# 1_flatsat_interfaces.net
KiCad netlist of a schematic drawn in Altium Designer
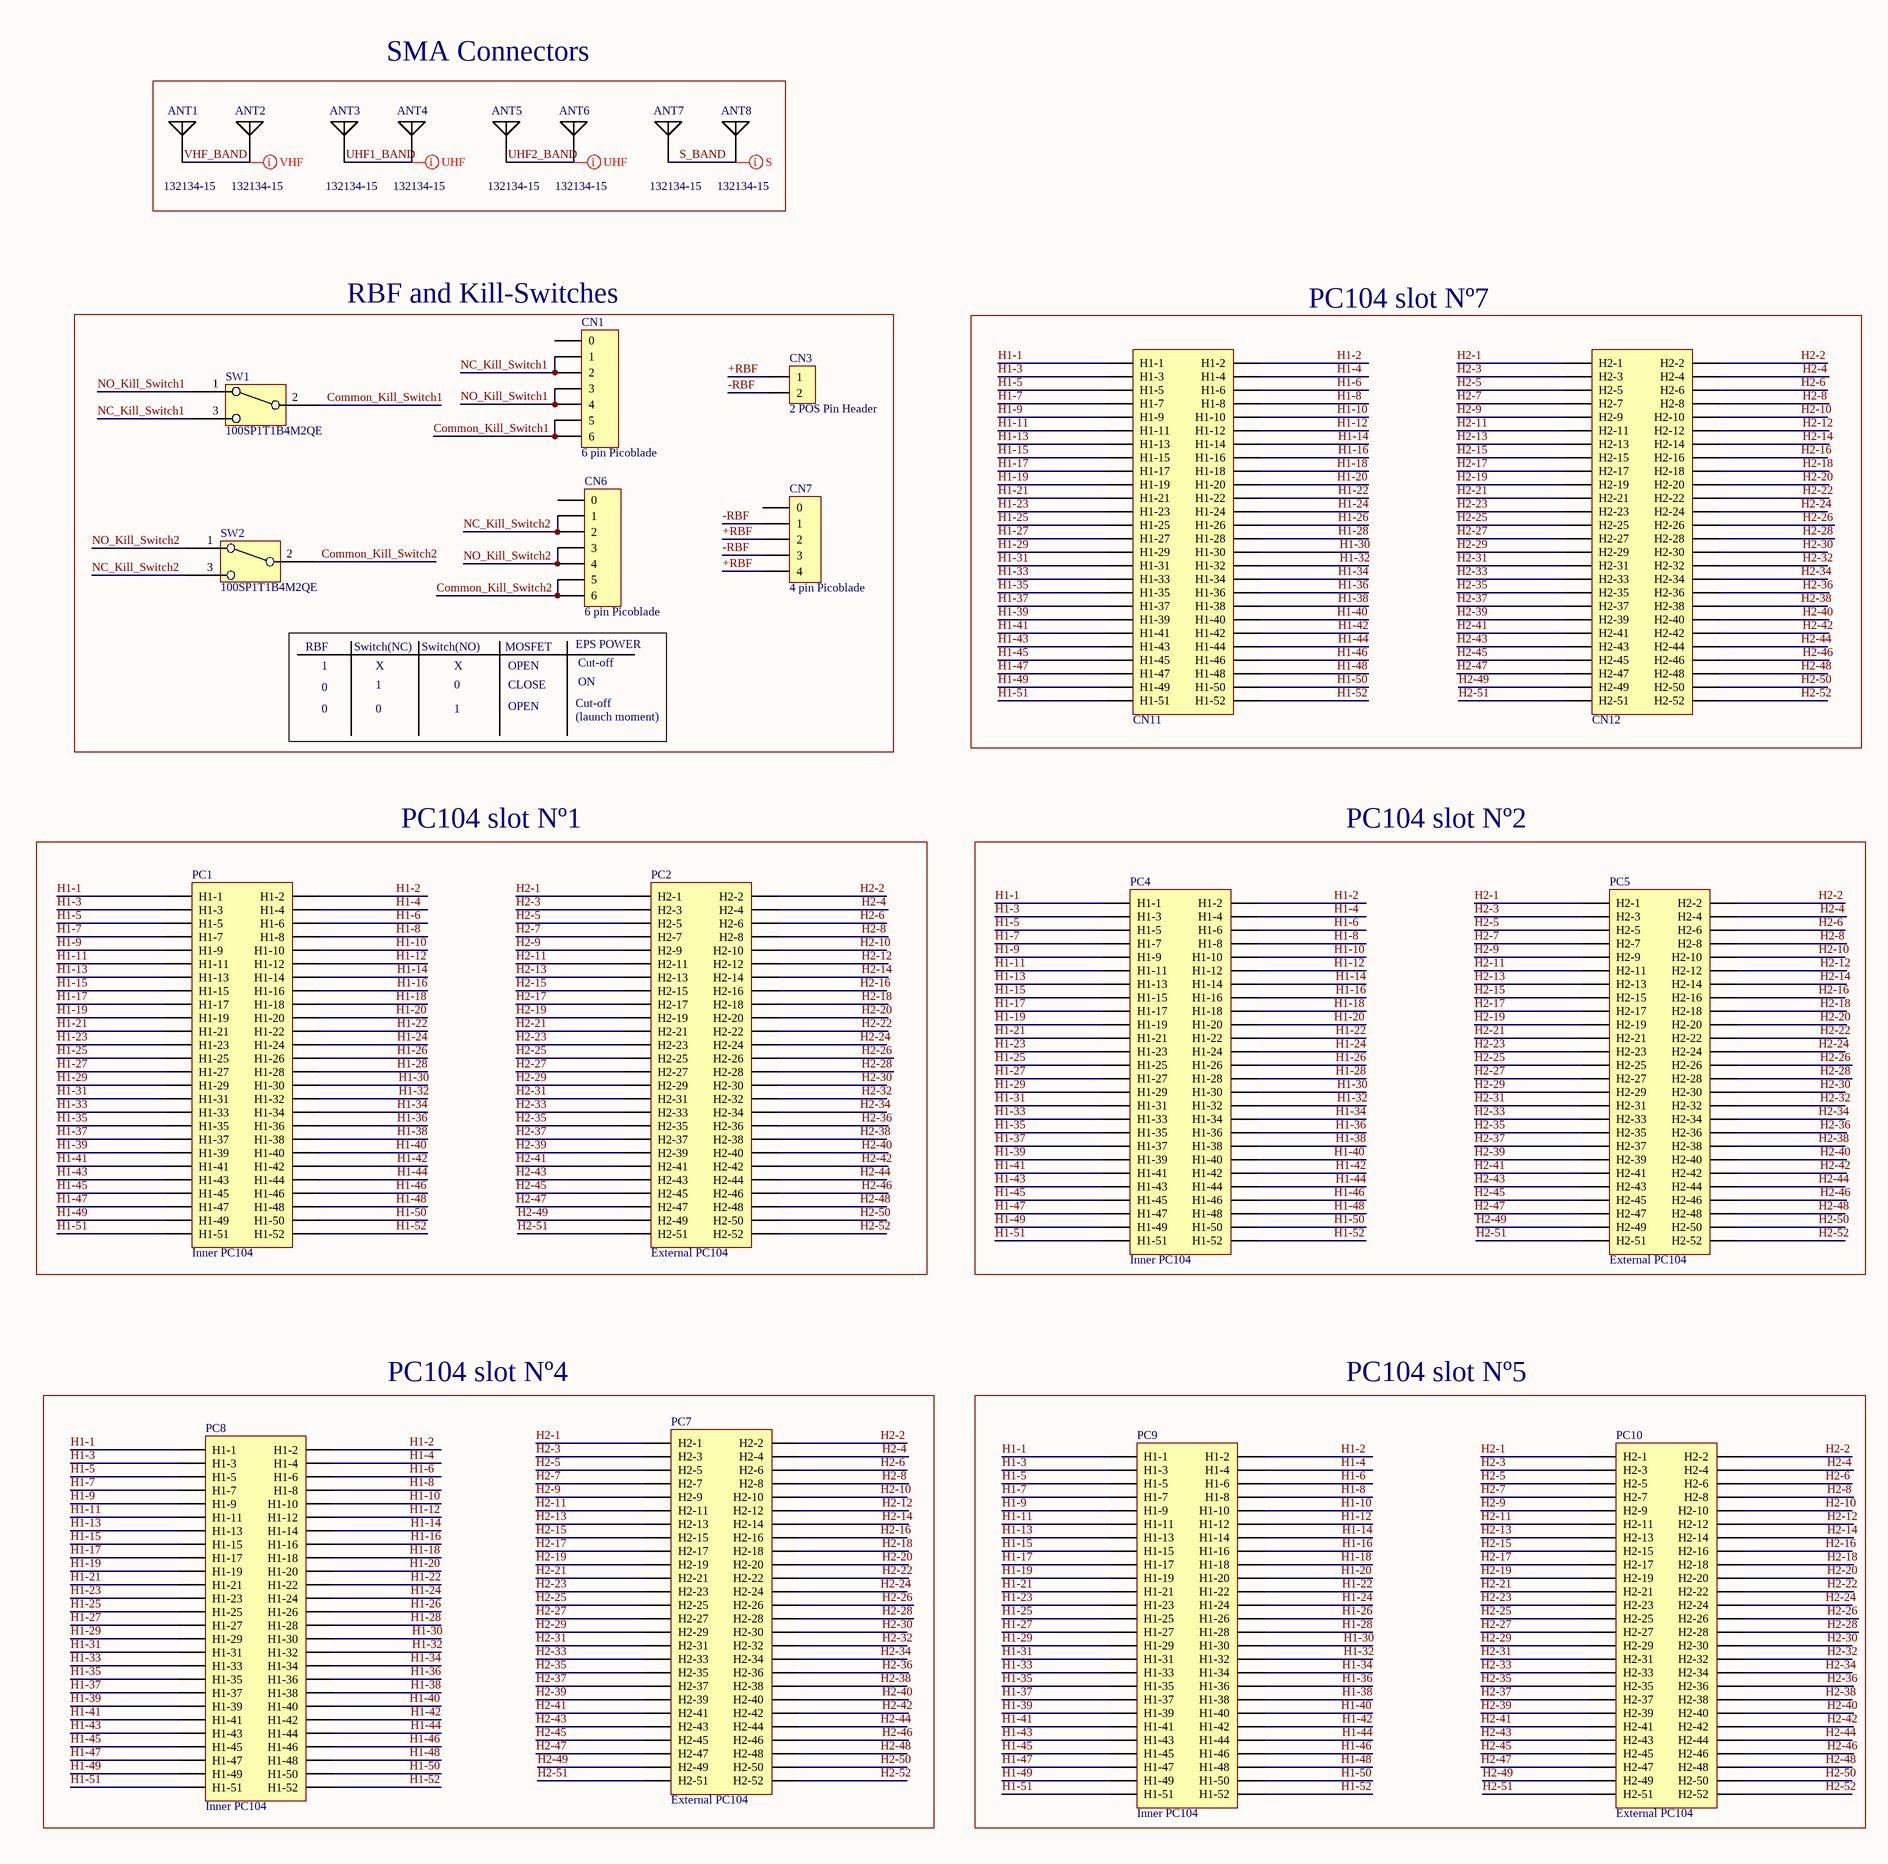
[diagram p0: 1_flatsat_interfaces.SchDoc, left]
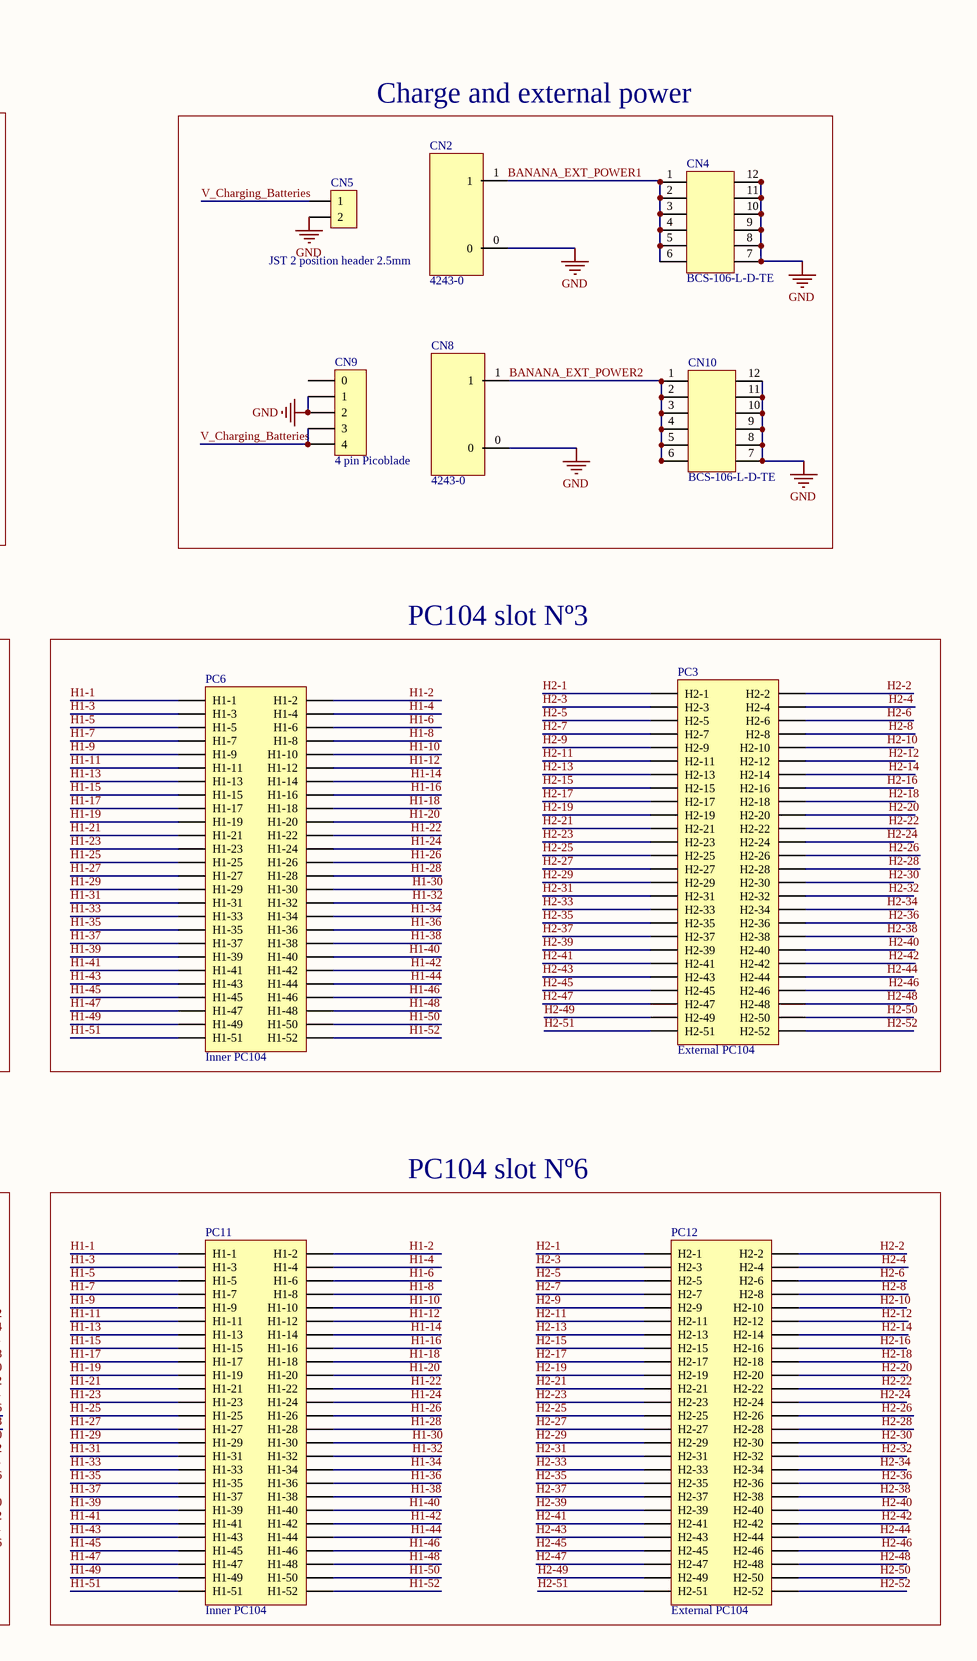
[diagram p1: 1_flatsat_interfaces.SchDoc, right]

(export (version "E")
  (design (tool "Eeschema 10.0.6"))
  (components
    (comp (ref "ANT1")
      (value "132134-15")
      (footprint "132134-15")
      (libsource (lib "flatsat_platform") (part "132134-15"))
    )
    (comp (ref "ANT2")
      (value "132134-15")
      (footprint "132134-15")
      (libsource (lib "flatsat_platform") (part "132134-15"))
    )
    (comp (ref "ANT3")
      (value "132134-15")
      (footprint "132134-15")
      (libsource (lib "flatsat_platform") (part "132134-15"))
    )
    (comp (ref "ANT4")
      (value "132134-15")
      (footprint "132134-15")
      (libsource (lib "flatsat_platform") (part "132134-15"))
    )
    (comp (ref "ANT5")
      (value "132134-15")
      (footprint "132134-15")
      (libsource (lib "flatsat_platform") (part "132134-15"))
    )
    (comp (ref "ANT6")
      (value "132134-15")
      (footprint "132134-15")
      (libsource (lib "flatsat_platform") (part "132134-15"))
    )
    (comp (ref "ANT7")
      (value "132134-15")
      (footprint "132134-15")
      (libsource (lib "flatsat_platform") (part "132134-15"))
    )
    (comp (ref "ANT8")
      (value "132134-15")
      (footprint "132134-15")
      (libsource (lib "flatsat_platform") (part "132134-15"))
    )
    (comp (ref "CN1")
      (value "6 pin Picoblade")
      (footprint "PICO BLADE 0533980671")
      (description "1.25mm Pitch PicoBlade™ Header, Surface Mount, Vertical, 6 Circuits")
      (fields (field (name "MANUFACTURER") "Molex") (field (name "MANUFACTURER PART NUMBER") "53398-0671"))
      (libsource (lib "flatsat_platform") (part "53398-0671"))
    )
    (comp (ref "CN2")
      (value "4243-0")
      (footprint "4243-0")
      (description "POMONA, 4243-0, Binding Post, 4243 Series, 15 A, 60 VDC, Tin Plated Contacts, Brass, Black")
      (fields (field (name "MANUFACTURER") "Pomona Electronics"))
      (libsource (lib "flatsat_platform") (part "4243-0"))
    )
    (comp (ref "CN3")
      (value "2 POS Pin Header")
      (footprint "CONN HEADER VERT 2POS 2.54mm")
      (description "M20 HDR, PIN, SIL, VERT, 2W")
      (fields (field (name "MANUFACTURER") "Harwin") (field (name "VOLTAGE") "50V"))
      (libsource (lib "flatsat_platform") (part "M20-9990245"))
    )
    (comp (ref "CN4")
      (value "BCS-106-L-D-TE")
      (footprint "BCS-106-L-D-TE")
      (description "CONN RCPT 12POS 0.1 GOLD PCB")
      (fields (field (name "MANUFACTURER") "Samtec"))
      (libsource (lib "flatsat_platform") (part "BCS-106-L-D-TE"))
    )
    (comp (ref "CN5")
      (value "JST 2 position header 2.5mm")
      (footprint "B2B-XH-A-M(LF)(SN)")
      (description "CONN HEADER TOP 2POS 2.5MM GRN")
      (fields
        (field (name "MANUFACTURER") "JST")
        (field (name "MANUFACTURER PART NUMBER") "B2B-XH-A-M(LF)(SN)")
      )
      (libsource (lib "flatsat_platform") (part "B2B-XH-A-M(LF)(SN)"))
    )
    (comp (ref "CN6")
      (value "6 pin Picoblade")
      (footprint "PICO BLADE 0533980671")
      (description "1.25mm Pitch PicoBlade™ Header, Surface Mount, Vertical, 6 Circuits")
      (fields (field (name "MANUFACTURER") "Molex") (field (name "MANUFACTURER PART NUMBER") "53398-0671"))
      (libsource (lib "flatsat_platform") (part "53398-0671"))
    )
    (comp (ref "CN7")
      (value "4 pin Picoblade")
      (footprint "PICO BLADE 0533980471")
      (description "Connector Header Surface Mount 4 position 0.049\" (1.25mm)")
      (fields (field (name "MANUFACTURER") "Molex") (field (name "MANUFACTURER PART NUMBER") "53398-0471"))
      (libsource (lib "flatsat_platform") (part "0533980471"))
    )
    (comp (ref "CN8")
      (value "4243-0")
      (footprint "4243-0")
      (description "POMONA, 4243-0, Binding Post, 4243 Series, 15 A, 60 VDC, Tin Plated Contacts, Brass, Black")
      (fields (field (name "MANUFACTURER") "Pomona Electronics"))
      (libsource (lib "flatsat_platform") (part "4243-0"))
    )
    (comp (ref "CN9")
      (value "4 pin Picoblade")
      (footprint "PICO BLADE 0533980471")
      (description "Connector Header Surface Mount 4 position 0.049\" (1.25mm)")
      (fields (field (name "MANUFACTURER") "Molex") (field (name "MANUFACTURER PART NUMBER") "53398-0471"))
      (libsource (lib "flatsat_platform") (part "0533980471"))
    )
    (comp (ref "CN10")
      (value "BCS-106-L-D-TE")
      (footprint "BCS-106-L-D-TE")
      (description "CONN RCPT 12POS 0.1 GOLD PCB")
      (fields (field (name "MANUFACTURER") "Samtec"))
      (libsource (lib "flatsat_platform") (part "BCS-106-L-D-TE"))
    )
    (comp (ref "CN11")
      (value "CONN RCPT 52POS 0.1 GOLD PCB")
      (footprint "Inner_SSW-126-01-G-D_testboard")
      (description "Conn Socket Strip SKT 52 POS 2.54mm Solder ST Thru-Hole")
      (fields
        (field (name "MANUFACTURER") "Samtec")
        (field (name "MANUFACTURER PART NUMBER") "SSW-126-01-G-D")
      )
      (libsource (lib "flatsat_platform") (part "Inner_Expansion_TestBoard_PC104"))
    )
    (comp (ref "CN12")
      (value "CONN RCPT 52POS 0.1 GOLD PCB")
      (footprint "external_SSW-126-01-G-D _testboard")
      (description "Conn Socket Strip SKT 52 POS 2.54mm Solder ST Thru-Hole")
      (fields
        (field (name "MANUFACTURER") "Samtec")
        (field (name "MANUFACTURER PART NUMBER") "SSW-126-01-G-D")
      )
      (libsource (lib "flatsat_platform") (part "External_Expansion_TestBoard_PC104"))
    )
    (comp (ref "PC1")
      (value "Inner PC104")
      (footprint "Inner_SSW-126-01-G-D")
      (description "52 Position Receptacle Connector  Through Hole")
      (fields (field (name "PARTNUMBER") "SSW-126-01-G-D") (field (name "MANUFACTURER") "Samtec"))
      (libsource (lib "flatsat_platform") (part "Inner_SSW-126-01-G-D"))
    )
    (comp (ref "PC2")
      (value "External PC104")
      (footprint "external_SSW-126-01-G-D")
      (description "52 Position Receptacle Connector  Through Hole")
      (fields (field (name "PARTNUMBER") "SSW-126-01-G-D") (field (name "MANUFACTURER") "Samtec"))
      (libsource (lib "flatsat_platform") (part "External_SSW-126-01-G-D_1"))
    )
    (comp (ref "PC3")
      (value "External PC104")
      (footprint "external_SSW-126-01-G-D")
      (description "52 Position Receptacle Connector  Through Hole")
      (fields (field (name "PARTNUMBER") "SSW-126-01-G-D") (field (name "MANUFACTURER") "Samtec"))
      (libsource (lib "flatsat_platform") (part "External_SSW-126-01-G-D_1"))
    )
    (comp (ref "PC4")
      (value "Inner PC104")
      (footprint "Inner_SSW-126-01-G-D")
      (description "52 Position Receptacle Connector  Through Hole")
      (fields (field (name "PARTNUMBER") "SSW-126-01-G-D") (field (name "MANUFACTURER") "Samtec"))
      (libsource (lib "flatsat_platform") (part "Inner_SSW-126-01-G-D"))
    )
    (comp (ref "PC5")
      (value "External PC104")
      (footprint "external_SSW-126-01-G-D")
      (description "52 Position Receptacle Connector  Through Hole")
      (fields (field (name "PARTNUMBER") "SSW-126-01-G-D") (field (name "MANUFACTURER") "Samtec"))
      (libsource (lib "flatsat_platform") (part "External_SSW-126-01-G-D_1"))
    )
    (comp (ref "PC6")
      (value "Inner PC104")
      (footprint "Inner_SSW-126-01-G-D")
      (description "52 Position Receptacle Connector  Through Hole")
      (fields (field (name "PARTNUMBER") "SSW-126-01-G-D") (field (name "MANUFACTURER") "Samtec"))
      (libsource (lib "flatsat_platform") (part "Inner_SSW-126-01-G-D"))
    )
    (comp (ref "PC7")
      (value "External PC104")
      (footprint "external_SSW-126-01-G-D")
      (description "52 Position Receptacle Connector  Through Hole")
      (fields (field (name "PARTNUMBER") "SSW-126-01-G-D") (field (name "MANUFACTURER") "Samtec"))
      (libsource (lib "flatsat_platform") (part "External_SSW-126-01-G-D_1"))
    )
    (comp (ref "PC8")
      (value "Inner PC104")
      (footprint "Inner_SSW-126-01-G-D")
      (description "52 Position Receptacle Connector  Through Hole")
      (fields (field (name "PARTNUMBER") "SSW-126-01-G-D") (field (name "MANUFACTURER") "Samtec"))
      (libsource (lib "flatsat_platform") (part "Inner_SSW-126-01-G-D"))
    )
    (comp (ref "PC9")
      (value "Inner PC104")
      (footprint "Inner_SSW-126-01-G-D")
      (description "52 Position Receptacle Connector  Through Hole")
      (fields (field (name "PARTNUMBER") "SSW-126-01-G-D") (field (name "MANUFACTURER") "Samtec"))
      (libsource (lib "flatsat_platform") (part "Inner_SSW-126-01-G-D"))
    )
    (comp (ref "PC10")
      (value "External PC104")
      (footprint "external_SSW-126-01-G-D")
      (description "52 Position Receptacle Connector  Through Hole")
      (fields (field (name "PARTNUMBER") "SSW-126-01-G-D") (field (name "MANUFACTURER") "Samtec"))
      (libsource (lib "flatsat_platform") (part "External_SSW-126-01-G-D_1"))
    )
    (comp (ref "PC11")
      (value "Inner PC104")
      (footprint "Inner_SSW-126-01-G-D")
      (description "52 Position Receptacle Connector  Through Hole")
      (fields (field (name "PARTNUMBER") "SSW-126-01-G-D") (field (name "MANUFACTURER") "Samtec"))
      (libsource (lib "flatsat_platform") (part "Inner_SSW-126-01-G-D"))
    )
    (comp (ref "PC12")
      (value "External PC104")
      (footprint "external_SSW-126-01-G-D")
      (description "52 Position Receptacle Connector  Through Hole")
      (fields (field (name "PARTNUMBER") "SSW-126-01-G-D") (field (name "MANUFACTURER") "Samtec"))
      (libsource (lib "flatsat_platform") (part "External_SSW-126-01-G-D_1"))
    )
    (comp (ref "SW1")
      (value "100SP1T1B4M2QE")
      (footprint "Toggle Switch SPDT Through Hole")
      (description "E-SWITCH - 100SP1T1B4M2QE - SWITCH, TOGGLE, SPDT, 5A, 120VAC, 28VDC")
      (libsource (lib "flatsat_platform") (part "100SP1T1B4M2QE"))
    )
    (comp (ref "SW2")
      (value "100SP1T1B4M2QE")
      (footprint "Toggle Switch SPDT Through Hole")
      (description "E-SWITCH - 100SP1T1B4M2QE - SWITCH, TOGGLE, SPDT, 5A, 120VAC, 28VDC")
      (libsource (lib "flatsat_platform") (part "100SP1T1B4M2QE"))
    )
  )
  (nets
    (net (code "1") (name "/+RBF") (class "Default")
      (node (ref "CN3") (pin "1") (pinfunction "1_1") (pintype "passive"))
      (node (ref "CN7") (pin "2") (pinfunction "2_2") (pintype "passive"))
      (node (ref "CN7") (pin "4") (pinfunction "4_4") (pintype "passive"))
    )
    (net (code "2") (name "/-RBF") (class "Default")
      (node (ref "CN3") (pin "2") (pinfunction "2_2") (pintype "passive"))
      (node (ref "CN7") (pin "1") (pinfunction "1_1") (pintype "passive"))
      (node (ref "CN7") (pin "3") (pinfunction "3_3") (pintype "passive"))
    )
    (net (code "3") (name "/BANANA_EXT_POWER1") (class "Default")
      (node (ref "CN2") (pin "1") (pinfunction "1_1") (pintype "passive"))
      (node (ref "CN4") (pin "1") (pintype "passive"))
      (node (ref "CN4") (pin "2") (pintype "passive"))
      (node (ref "CN4") (pin "3") (pintype "passive"))
      (node (ref "CN4") (pin "4") (pintype "passive"))
      (node (ref "CN4") (pin "5") (pintype "passive"))
      (node (ref "CN4") (pin "6") (pintype "passive"))
    )
    (net (code "4") (name "/BANANA_EXT_POWER2") (class "Default")
      (node (ref "CN10") (pin "1") (pintype "passive"))
      (node (ref "CN10") (pin "2") (pintype "passive"))
      (node (ref "CN10") (pin "3") (pintype "passive"))
      (node (ref "CN10") (pin "4") (pintype "passive"))
      (node (ref "CN10") (pin "5") (pintype "passive"))
      (node (ref "CN10") (pin "6") (pintype "passive"))
      (node (ref "CN8") (pin "1") (pinfunction "1_1") (pintype "passive"))
    )
    (net (code "5") (name "/Common_Kill_Switch1") (class "Default")
      (node (ref "CN1") (pin "5") (pinfunction "5_5") (pintype "passive"))
      (node (ref "CN1") (pin "6") (pinfunction "6_6") (pintype "passive"))
      (node (ref "SW1") (pin "2") (pinfunction "C_2") (pintype "passive"))
    )
    (net (code "6") (name "/Common_Kill_Switch2") (class "Default")
      (node (ref "CN6") (pin "5") (pinfunction "5_5") (pintype "passive"))
      (node (ref "CN6") (pin "6") (pinfunction "6_6") (pintype "passive"))
      (node (ref "SW2") (pin "2") (pinfunction "C_2") (pintype "passive"))
    )
    (net (code "7") (name "/H1-1") (class "Default")
      (node (ref "CN11") (pin "H1-1") (pinfunction "H1-1_H1-1") (pintype "passive"))
      (node (ref "PC1") (pin "H1-1") (pinfunction "H1-1_H1-1") (pintype "passive"))
      (node (ref "PC11") (pin "H1-1") (pinfunction "H1-1_H1-1") (pintype "passive"))
      (node (ref "PC4") (pin "H1-1") (pinfunction "H1-1_H1-1") (pintype "passive"))
      (node (ref "PC6") (pin "H1-1") (pinfunction "H1-1_H1-1") (pintype "passive"))
      (node (ref "PC8") (pin "H1-1") (pinfunction "H1-1_H1-1") (pintype "passive"))
      (node (ref "PC9") (pin "H1-1") (pinfunction "H1-1_H1-1") (pintype "passive"))
    )
    (net (code "8") (name "/H1-2") (class "Default")
      (node (ref "CN11") (pin "H1-2") (pinfunction "H1-2_H1-2") (pintype "passive"))
      (node (ref "PC1") (pin "H1-2") (pinfunction "H1-2_H1-2") (pintype "passive"))
      (node (ref "PC11") (pin "H1-2") (pinfunction "H1-2_H1-2") (pintype "passive"))
      (node (ref "PC4") (pin "H1-2") (pinfunction "H1-2_H1-2") (pintype "passive"))
      (node (ref "PC6") (pin "H1-2") (pinfunction "H1-2_H1-2") (pintype "passive"))
      (node (ref "PC8") (pin "H1-2") (pinfunction "H1-2_H1-2") (pintype "passive"))
      (node (ref "PC9") (pin "H1-2") (pinfunction "H1-2_H1-2") (pintype "passive"))
    )
    (net (code "9") (name "/H1-3") (class "Default")
      (node (ref "CN11") (pin "H1-3") (pinfunction "H1-3_H1-3") (pintype "passive"))
      (node (ref "PC1") (pin "H1-3") (pinfunction "H1-3_H1-3") (pintype "passive"))
      (node (ref "PC11") (pin "H1-3") (pinfunction "H1-3_H1-3") (pintype "passive"))
      (node (ref "PC4") (pin "H1-3") (pinfunction "H1-3_H1-3") (pintype "passive"))
      (node (ref "PC6") (pin "H1-3") (pinfunction "H1-3_H1-3") (pintype "passive"))
      (node (ref "PC8") (pin "H1-3") (pinfunction "H1-3_H1-3") (pintype "passive"))
      (node (ref "PC9") (pin "H1-3") (pinfunction "H1-3_H1-3") (pintype "passive"))
    )
    (net (code "10") (name "/H1-4") (class "Default")
      (node (ref "CN11") (pin "H1-4") (pinfunction "H1-4_H1-4") (pintype "passive"))
      (node (ref "PC1") (pin "H1-4") (pinfunction "H1-4_H1-4") (pintype "passive"))
      (node (ref "PC11") (pin "H1-4") (pinfunction "H1-4_H1-4") (pintype "passive"))
      (node (ref "PC4") (pin "H1-4") (pinfunction "H1-4_H1-4") (pintype "passive"))
      (node (ref "PC6") (pin "H1-4") (pinfunction "H1-4_H1-4") (pintype "passive"))
      (node (ref "PC8") (pin "H1-4") (pinfunction "H1-4_H1-4") (pintype "passive"))
      (node (ref "PC9") (pin "H1-4") (pinfunction "H1-4_H1-4") (pintype "passive"))
    )
    (net (code "11") (name "/H1-5") (class "Default")
      (node (ref "CN11") (pin "H1-5") (pinfunction "H1-5_H1-5") (pintype "passive"))
      (node (ref "PC1") (pin "H1-5") (pinfunction "H1-5_H1-5") (pintype "passive"))
      (node (ref "PC11") (pin "H1-5") (pinfunction "H1-5_H1-5") (pintype "passive"))
      (node (ref "PC4") (pin "H1-5") (pinfunction "H1-5_H1-5") (pintype "passive"))
      (node (ref "PC6") (pin "H1-5") (pinfunction "H1-5_H1-5") (pintype "passive"))
      (node (ref "PC8") (pin "H1-5") (pinfunction "H1-5_H1-5") (pintype "passive"))
      (node (ref "PC9") (pin "H1-5") (pinfunction "H1-5_H1-5") (pintype "passive"))
    )
    (net (code "12") (name "/H1-6") (class "Default")
      (node (ref "CN11") (pin "H1-6") (pinfunction "H1-6_H1-6") (pintype "passive"))
      (node (ref "PC1") (pin "H1-6") (pinfunction "H1-6_H1-6") (pintype "passive"))
      (node (ref "PC11") (pin "H1-6") (pinfunction "H1-6_H1-6") (pintype "passive"))
      (node (ref "PC4") (pin "H1-6") (pinfunction "H1-6_H1-6") (pintype "passive"))
      (node (ref "PC6") (pin "H1-6") (pinfunction "H1-6_H1-6") (pintype "passive"))
      (node (ref "PC8") (pin "H1-6") (pinfunction "H1-6_H1-6") (pintype "passive"))
      (node (ref "PC9") (pin "H1-6") (pinfunction "H1-6_H1-6") (pintype "passive"))
    )
    (net (code "13") (name "/H1-7") (class "Default")
      (node (ref "CN11") (pin "H1-7") (pinfunction "H1-7_H1-7") (pintype "passive"))
      (node (ref "PC1") (pin "H1-7") (pinfunction "H1-7_H1-7") (pintype "passive"))
      (node (ref "PC11") (pin "H1-7") (pinfunction "H1-7_H1-7") (pintype "passive"))
      (node (ref "PC4") (pin "H1-7") (pinfunction "H1-7_H1-7") (pintype "passive"))
      (node (ref "PC6") (pin "H1-7") (pinfunction "H1-7_H1-7") (pintype "passive"))
      (node (ref "PC8") (pin "H1-7") (pinfunction "H1-7_H1-7") (pintype "passive"))
      (node (ref "PC9") (pin "H1-7") (pinfunction "H1-7_H1-7") (pintype "passive"))
    )
    (net (code "14") (name "/H1-8") (class "Default")
      (node (ref "CN11") (pin "H1-8") (pinfunction "H1-8_H1-8") (pintype "passive"))
      (node (ref "PC1") (pin "H1-8") (pinfunction "H1-8_H1-8") (pintype "passive"))
      (node (ref "PC11") (pin "H1-8") (pinfunction "H1-8_H1-8") (pintype "passive"))
      (node (ref "PC4") (pin "H1-8") (pinfunction "H1-8_H1-8") (pintype "passive"))
      (node (ref "PC6") (pin "H1-8") (pinfunction "H1-8_H1-8") (pintype "passive"))
      (node (ref "PC8") (pin "H1-8") (pinfunction "H1-8_H1-8") (pintype "passive"))
      (node (ref "PC9") (pin "H1-8") (pinfunction "H1-8_H1-8") (pintype "passive"))
    )
    (net (code "15") (name "/H1-9") (class "Default")
      (node (ref "CN11") (pin "H1-9") (pinfunction "H1-9_H1-9") (pintype "passive"))
      (node (ref "PC1") (pin "H1-9") (pinfunction "H1-9_H1-9") (pintype "passive"))
      (node (ref "PC11") (pin "H1-9") (pinfunction "H1-9_H1-9") (pintype "passive"))
      (node (ref "PC4") (pin "H1-9") (pinfunction "H1-9_H1-9") (pintype "passive"))
      (node (ref "PC6") (pin "H1-9") (pinfunction "H1-9_H1-9") (pintype "passive"))
      (node (ref "PC8") (pin "H1-9") (pinfunction "H1-9_H1-9") (pintype "passive"))
      (node (ref "PC9") (pin "H1-9") (pinfunction "H1-9_H1-9") (pintype "passive"))
    )
    (net (code "16") (name "/H1-10") (class "Default")
      (node (ref "CN11") (pin "H1-10") (pinfunction "H1-10_H1-10") (pintype "passive"))
      (node (ref "PC1") (pin "H1-10") (pinfunction "H1-10_H1-10") (pintype "passive"))
      (node (ref "PC11") (pin "H1-10") (pinfunction "H1-10_H1-10") (pintype "passive"))
      (node (ref "PC4") (pin "H1-10") (pinfunction "H1-10_H1-10") (pintype "passive"))
      (node (ref "PC6") (pin "H1-10") (pinfunction "H1-10_H1-10") (pintype "passive"))
      (node (ref "PC8") (pin "H1-10") (pinfunction "H1-10_H1-10") (pintype "passive"))
      (node (ref "PC9") (pin "H1-10") (pinfunction "H1-10_H1-10") (pintype "passive"))
    )
    (net (code "17") (name "/H1-11") (class "Default")
      (node (ref "CN11") (pin "H1-11") (pinfunction "H1-11_H1-11") (pintype "passive"))
      (node (ref "PC1") (pin "H1-11") (pinfunction "H1-11_H1-11") (pintype "passive"))
      (node (ref "PC11") (pin "H1-11") (pinfunction "H1-11_H1-11") (pintype "passive"))
      (node (ref "PC4") (pin "H1-11") (pinfunction "H1-11_H1-11") (pintype "passive"))
      (node (ref "PC6") (pin "H1-11") (pinfunction "H1-11_H1-11") (pintype "passive"))
      (node (ref "PC8") (pin "H1-11") (pinfunction "H1-11_H1-11") (pintype "passive"))
      (node (ref "PC9") (pin "H1-11") (pinfunction "H1-11_H1-11") (pintype "passive"))
    )
    (net (code "18") (name "/H1-12") (class "Default")
      (node (ref "CN11") (pin "H1-12") (pinfunction "H1-12_H1-12") (pintype "passive"))
      (node (ref "PC1") (pin "H1-12") (pinfunction "H1-12_H1-12") (pintype "passive"))
      (node (ref "PC11") (pin "H1-12") (pinfunction "H1-12_H1-12") (pintype "passive"))
      (node (ref "PC4") (pin "H1-12") (pinfunction "H1-12_H1-12") (pintype "passive"))
      (node (ref "PC6") (pin "H1-12") (pinfunction "H1-12_H1-12") (pintype "passive"))
      (node (ref "PC8") (pin "H1-12") (pinfunction "H1-12_H1-12") (pintype "passive"))
      (node (ref "PC9") (pin "H1-12") (pinfunction "H1-12_H1-12") (pintype "passive"))
    )
    (net (code "19") (name "/H1-13") (class "Default")
      (node (ref "CN11") (pin "H1-13") (pinfunction "H1-13_H1-13") (pintype "passive"))
      (node (ref "PC1") (pin "H1-13") (pinfunction "H1-13_H1-13") (pintype "passive"))
      (node (ref "PC11") (pin "H1-13") (pinfunction "H1-13_H1-13") (pintype "passive"))
      (node (ref "PC4") (pin "H1-13") (pinfunction "H1-13_H1-13") (pintype "passive"))
      (node (ref "PC6") (pin "H1-13") (pinfunction "H1-13_H1-13") (pintype "passive"))
      (node (ref "PC8") (pin "H1-13") (pinfunction "H1-13_H1-13") (pintype "passive"))
      (node (ref "PC9") (pin "H1-13") (pinfunction "H1-13_H1-13") (pintype "passive"))
    )
    (net (code "20") (name "/H1-14") (class "Default")
      (node (ref "CN11") (pin "H1-14") (pinfunction "H1-14_H1-14") (pintype "passive"))
      (node (ref "PC1") (pin "H1-14") (pinfunction "H1-14_H1-14") (pintype "passive"))
      (node (ref "PC11") (pin "H1-14") (pinfunction "H1-14_H1-14") (pintype "passive"))
      (node (ref "PC4") (pin "H1-14") (pinfunction "H1-14_H1-14") (pintype "passive"))
      (node (ref "PC6") (pin "H1-14") (pinfunction "H1-14_H1-14") (pintype "passive"))
      (node (ref "PC8") (pin "H1-14") (pinfunction "H1-14_H1-14") (pintype "passive"))
      (node (ref "PC9") (pin "H1-14") (pinfunction "H1-14_H1-14") (pintype "passive"))
    )
    (net (code "21") (name "/H1-15") (class "Default")
      (node (ref "CN11") (pin "H1-15") (pinfunction "H1-15_H1-15") (pintype "passive"))
      (node (ref "PC1") (pin "H1-15") (pinfunction "H1-15_H1-15") (pintype "passive"))
      (node (ref "PC11") (pin "H1-15") (pinfunction "H1-15_H1-15") (pintype "passive"))
      (node (ref "PC4") (pin "H1-15") (pinfunction "H1-15_H1-15") (pintype "passive"))
      (node (ref "PC6") (pin "H1-15") (pinfunction "H1-15_H1-15") (pintype "passive"))
      (node (ref "PC8") (pin "H1-15") (pinfunction "H1-15_H1-15") (pintype "passive"))
      (node (ref "PC9") (pin "H1-15") (pinfunction "H1-15_H1-15") (pintype "passive"))
    )
    (net (code "22") (name "/H1-16") (class "Default")
      (node (ref "CN11") (pin "H1-16") (pinfunction "H1-16_H1-16") (pintype "passive"))
      (node (ref "PC1") (pin "H1-16") (pinfunction "H1-16_H1-16") (pintype "passive"))
      (node (ref "PC11") (pin "H1-16") (pinfunction "H1-16_H1-16") (pintype "passive"))
      (node (ref "PC4") (pin "H1-16") (pinfunction "H1-16_H1-16") (pintype "passive"))
      (node (ref "PC6") (pin "H1-16") (pinfunction "H1-16_H1-16") (pintype "passive"))
      (node (ref "PC8") (pin "H1-16") (pinfunction "H1-16_H1-16") (pintype "passive"))
      (node (ref "PC9") (pin "H1-16") (pinfunction "H1-16_H1-16") (pintype "passive"))
    )
    (net (code "23") (name "/H1-17") (class "Default")
      (node (ref "CN11") (pin "H1-17") (pinfunction "H1-17_H1-17") (pintype "passive"))
      (node (ref "PC1") (pin "H1-17") (pinfunction "H1-17_H1-17") (pintype "passive"))
      (node (ref "PC11") (pin "H1-17") (pinfunction "H1-17_H1-17") (pintype "passive"))
      (node (ref "PC4") (pin "H1-17") (pinfunction "H1-17_H1-17") (pintype "passive"))
      (node (ref "PC6") (pin "H1-17") (pinfunction "H1-17_H1-17") (pintype "passive"))
      (node (ref "PC8") (pin "H1-17") (pinfunction "H1-17_H1-17") (pintype "passive"))
      (node (ref "PC9") (pin "H1-17") (pinfunction "H1-17_H1-17") (pintype "passive"))
    )
    (net (code "24") (name "/H1-18") (class "Default")
      (node (ref "CN11") (pin "H1-18") (pinfunction "H1-18_H1-18") (pintype "passive"))
      (node (ref "PC1") (pin "H1-18") (pinfunction "H1-18_H1-18") (pintype "passive"))
      (node (ref "PC11") (pin "H1-18") (pinfunction "H1-18_H1-18") (pintype "passive"))
      (node (ref "PC4") (pin "H1-18") (pinfunction "H1-18_H1-18") (pintype "passive"))
      (node (ref "PC6") (pin "H1-18") (pinfunction "H1-18_H1-18") (pintype "passive"))
      (node (ref "PC8") (pin "H1-18") (pinfunction "H1-18_H1-18") (pintype "passive"))
      (node (ref "PC9") (pin "H1-18") (pinfunction "H1-18_H1-18") (pintype "passive"))
    )
    (net (code "25") (name "/H1-19") (class "Default")
      (node (ref "CN11") (pin "H1-19") (pinfunction "H1-19_H1-19") (pintype "passive"))
      (node (ref "PC1") (pin "H1-19") (pinfunction "H1-19_H1-19") (pintype "passive"))
      (node (ref "PC11") (pin "H1-19") (pinfunction "H1-19_H1-19") (pintype "passive"))
      (node (ref "PC4") (pin "H1-19") (pinfunction "H1-19_H1-19") (pintype "passive"))
      (node (ref "PC6") (pin "H1-19") (pinfunction "H1-19_H1-19") (pintype "passive"))
      (node (ref "PC8") (pin "H1-19") (pinfunction "H1-19_H1-19") (pintype "passive"))
      (node (ref "PC9") (pin "H1-19") (pinfunction "H1-19_H1-19") (pintype "passive"))
    )
    (net (code "26") (name "/H1-20") (class "Default")
      (node (ref "CN11") (pin "H1-20") (pinfunction "H1-20_H1-20") (pintype "passive"))
      (node (ref "PC1") (pin "H1-20") (pinfunction "H1-20_H1-20") (pintype "passive"))
      (node (ref "PC11") (pin "H1-20") (pinfunction "H1-20_H1-20") (pintype "passive"))
      (node (ref "PC4") (pin "H1-20") (pinfunction "H1-20_H1-20") (pintype "passive"))
      (node (ref "PC6") (pin "H1-20") (pinfunction "H1-20_H1-20") (pintype "passive"))
      (node (ref "PC8") (pin "H1-20") (pinfunction "H1-20_H1-20") (pintype "passive"))
      (node (ref "PC9") (pin "H1-20") (pinfunction "H1-20_H1-20") (pintype "passive"))
    )
    (net (code "27") (name "/H1-21") (class "Default")
      (node (ref "CN11") (pin "H1-21") (pinfunction "H1-21_H1-21") (pintype "passive"))
      (node (ref "PC1") (pin "H1-21") (pinfunction "H1-21_H1-21") (pintype "passive"))
      (node (ref "PC11") (pin "H1-21") (pinfunction "H1-21_H1-21") (pintype "passive"))
      (node (ref "PC4") (pin "H1-21") (pinfunction "H1-21_H1-21") (pintype "passive"))
      (node (ref "PC6") (pin "H1-21") (pinfunction "H1-21_H1-21") (pintype "passive"))
      (node (ref "PC8") (pin "H1-21") (pinfunction "H1-21_H1-21") (pintype "passive"))
      (node (ref "PC9") (pin "H1-21") (pinfunction "H1-21_H1-21") (pintype "passive"))
    )
    (net (code "28") (name "/H1-22") (class "Default")
      (node (ref "CN11") (pin "H1-22") (pinfunction "H1-22_H1-22") (pintype "passive"))
      (node (ref "PC1") (pin "H1-22") (pinfunction "H1-22_H1-22") (pintype "passive"))
      (node (ref "PC11") (pin "H1-22") (pinfunction "H1-22_H1-22") (pintype "passive"))
      (node (ref "PC4") (pin "H1-22") (pinfunction "H1-22_H1-22") (pintype "passive"))
      (node (ref "PC6") (pin "H1-22") (pinfunction "H1-22_H1-22") (pintype "passive"))
      (node (ref "PC8") (pin "H1-22") (pinfunction "H1-22_H1-22") (pintype "passive"))
      (node (ref "PC9") (pin "H1-22") (pinfunction "H1-22_H1-22") (pintype "passive"))
    )
    (net (code "29") (name "/H1-23") (class "Default")
      (node (ref "CN11") (pin "H1-23") (pinfunction "H1-23_H1-23") (pintype "passive"))
      (node (ref "PC1") (pin "H1-23") (pinfunction "H1-23_H1-23") (pintype "passive"))
      (node (ref "PC11") (pin "H1-23") (pinfunction "H1-23_H1-23") (pintype "passive"))
      (node (ref "PC4") (pin "H1-23") (pinfunction "H1-23_H1-23") (pintype "passive"))
      (node (ref "PC6") (pin "H1-23") (pinfunction "H1-23_H1-23") (pintype "passive"))
      (node (ref "PC8") (pin "H1-23") (pinfunction "H1-23_H1-23") (pintype "passive"))
      (node (ref "PC9") (pin "H1-23") (pinfunction "H1-23_H1-23") (pintype "passive"))
    )
    (net (code "30") (name "/H1-24") (class "Default")
      (node (ref "CN11") (pin "H1-24") (pinfunction "H1-24_H1-24") (pintype "passive"))
      (node (ref "PC1") (pin "H1-24") (pinfunction "H1-24_H1-24") (pintype "passive"))
      (node (ref "PC11") (pin "H1-24") (pinfunction "H1-24_H1-24") (pintype "passive"))
      (node (ref "PC4") (pin "H1-24") (pinfunction "H1-24_H1-24") (pintype "passive"))
      (node (ref "PC6") (pin "H1-24") (pinfunction "H1-24_H1-24") (pintype "passive"))
      (node (ref "PC8") (pin "H1-24") (pinfunction "H1-24_H1-24") (pintype "passive"))
      (node (ref "PC9") (pin "H1-24") (pinfunction "H1-24_H1-24") (pintype "passive"))
    )
    (net (code "31") (name "/H1-25") (class "Default")
      (node (ref "CN11") (pin "H1-25") (pinfunction "H1-25_H1-25") (pintype "passive"))
      (node (ref "PC1") (pin "H1-25") (pinfunction "H1-25_H1-25") (pintype "passive"))
      (node (ref "PC11") (pin "H1-25") (pinfunction "H1-25_H1-25") (pintype "passive"))
      (node (ref "PC4") (pin "H1-25") (pinfunction "H1-25_H1-25") (pintype "passive"))
      (node (ref "PC6") (pin "H1-25") (pinfunction "H1-25_H1-25") (pintype "passive"))
      (node (ref "PC8") (pin "H1-25") (pinfunction "H1-25_H1-25") (pintype "passive"))
      (node (ref "PC9") (pin "H1-25") (pinfunction "H1-25_H1-25") (pintype "passive"))
    )
    (net (code "32") (name "/H1-26") (class "Default")
      (node (ref "CN11") (pin "H1-26") (pinfunction "H1-26_H1-26") (pintype "passive"))
      (node (ref "PC1") (pin "H1-26") (pinfunction "H1-26_H1-26") (pintype "passive"))
      (node (ref "PC11") (pin "H1-26") (pinfunction "H1-26_H1-26") (pintype "passive"))
      (node (ref "PC4") (pin "H1-26") (pinfunction "H1-26_H1-26") (pintype "passive"))
      (node (ref "PC6") (pin "H1-26") (pinfunction "H1-26_H1-26") (pintype "passive"))
      (node (ref "PC8") (pin "H1-26") (pinfunction "H1-26_H1-26") (pintype "passive"))
      (node (ref "PC9") (pin "H1-26") (pinfunction "H1-26_H1-26") (pintype "passive"))
    )
    (net (code "33") (name "/H1-27") (class "Default")
      (node (ref "CN11") (pin "H1-27") (pinfunction "H1-27_H1-27") (pintype "passive"))
      (node (ref "PC1") (pin "H1-27") (pinfunction "H1-27_H1-27") (pintype "passive"))
      (node (ref "PC11") (pin "H1-27") (pinfunction "H1-27_H1-27") (pintype "passive"))
      (node (ref "PC4") (pin "H1-27") (pinfunction "H1-27_H1-27") (pintype "passive"))
      (node (ref "PC6") (pin "H1-27") (pinfunction "H1-27_H1-27") (pintype "passive"))
      (node (ref "PC8") (pin "H1-27") (pinfunction "H1-27_H1-27") (pintype "passive"))
      (node (ref "PC9") (pin "H1-27") (pinfunction "H1-27_H1-27") (pintype "passive"))
    )
    (net (code "34") (name "/H1-28") (class "Default")
      (node (ref "CN11") (pin "H1-28") (pinfunction "H1-28_H1-28") (pintype "passive"))
      (node (ref "PC1") (pin "H1-28") (pinfunction "H1-28_H1-28") (pintype "passive"))
      (node (ref "PC11") (pin "H1-28") (pinfunction "H1-28_H1-28") (pintype "passive"))
      (node (ref "PC4") (pin "H1-28") (pinfunction "H1-28_H1-28") (pintype "passive"))
      (node (ref "PC6") (pin "H1-28") (pinfunction "H1-28_H1-28") (pintype "passive"))
      (node (ref "PC8") (pin "H1-28") (pinfunction "H1-28_H1-28") (pintype "passive"))
      (node (ref "PC9") (pin "H1-28") (pinfunction "H1-28_H1-28") (pintype "passive"))
    )
    (net (code "35") (name "/H1-29") (class "Default")
      (node (ref "CN11") (pin "H1-29") (pinfunction "H1-29_H1-29") (pintype "passive"))
      (node (ref "PC1") (pin "H1-29") (pinfunction "H1-29_H1-29") (pintype "passive"))
      (node (ref "PC11") (pin "H1-29") (pinfunction "H1-29_H1-29") (pintype "passive"))
      (node (ref "PC4") (pin "H1-29") (pinfunction "H1-29_H1-29") (pintype "passive"))
      (node (ref "PC6") (pin "H1-29") (pinfunction "H1-29_H1-29") (pintype "passive"))
      (node (ref "PC8") (pin "H1-29") (pinfunction "H1-29_H1-29") (pintype "passive"))
      (node (ref "PC9") (pin "H1-29") (pinfunction "H1-29_H1-29") (pintype "passive"))
    )
    (net (code "36") (name "/H1-30") (class "Default")
      (node (ref "CN11") (pin "H1-30") (pinfunction "H1-30_H1-30") (pintype "passive"))
      (node (ref "PC1") (pin "H1-30") (pinfunction "H1-30_H1-30") (pintype "passive"))
      (node (ref "PC11") (pin "H1-30") (pinfunction "H1-30_H1-30") (pintype "passive"))
      (node (ref "PC4") (pin "H1-30") (pinfunction "H1-30_H1-30") (pintype "passive"))
      (node (ref "PC6") (pin "H1-30") (pinfunction "H1-30_H1-30") (pintype "passive"))
      (node (ref "PC8") (pin "H1-30") (pinfunction "H1-30_H1-30") (pintype "passive"))
      (node (ref "PC9") (pin "H1-30") (pinfunction "H1-30_H1-30") (pintype "passive"))
    )
    (net (code "37") (name "/H1-31") (class "Default")
      (node (ref "CN11") (pin "H1-31") (pinfunction "H1-31_H1-31") (pintype "passive"))
      (node (ref "PC1") (pin "H1-31") (pinfunction "H1-31_H1-31") (pintype "passive"))
      (node (ref "PC11") (pin "H1-31") (pinfunction "H1-31_H1-31") (pintype "passive"))
      (node (ref "PC4") (pin "H1-31") (pinfunction "H1-31_H1-31") (pintype "passive"))
      (node (ref "PC6") (pin "H1-31") (pinfunction "H1-31_H1-31") (pintype "passive"))
      (node (ref "PC8") (pin "H1-31") (pinfunction "H1-31_H1-31") (pintype "passive"))
      (node (ref "PC9") (pin "H1-31") (pinfunction "H1-31_H1-31") (pintype "passive"))
    )
    (net (code "38") (name "/H1-32") (class "Default")
      (node (ref "CN11") (pin "H1-32") (pinfunction "H1-32_H1-32") (pintype "passive"))
      (node (ref "PC1") (pin "H1-32") (pinfunction "H1-32_H1-32") (pintype "passive"))
      (node (ref "PC11") (pin "H1-32") (pinfunction "H1-32_H1-32") (pintype "passive"))
      (node (ref "PC4") (pin "H1-32") (pinfunction "H1-32_H1-32") (pintype "passive"))
      (node (ref "PC6") (pin "H1-32") (pinfunction "H1-32_H1-32") (pintype "passive"))
      (node (ref "PC8") (pin "H1-32") (pinfunction "H1-32_H1-32") (pintype "passive"))
      (node (ref "PC9") (pin "H1-32") (pinfunction "H1-32_H1-32") (pintype "passive"))
    )
    (net (code "39") (name "/H1-33") (class "Default")
      (node (ref "CN11") (pin "H1-33") (pinfunction "H1-33_H1-33") (pintype "passive"))
      (node (ref "PC1") (pin "H1-33") (pinfunction "H1-33_H1-33") (pintype "passive"))
      (node (ref "PC11") (pin "H1-33") (pinfunction "H1-33_H1-33") (pintype "passive"))
      (node (ref "PC4") (pin "H1-33") (pinfunction "H1-33_H1-33") (pintype "passive"))
      (node (ref "PC6") (pin "H1-33") (pinfunction "H1-33_H1-33") (pintype "passive"))
      (node (ref "PC8") (pin "H1-33") (pinfunction "H1-33_H1-33") (pintype "passive"))
      (node (ref "PC9") (pin "H1-33") (pinfunction "H1-33_H1-33") (pintype "passive"))
    )
    (net (code "40") (name "/H1-34") (class "Default")
      (node (ref "CN11") (pin "H1-34") (pinfunction "H1-34_H1-34") (pintype "passive"))
      (node (ref "PC1") (pin "H1-34") (pinfunction "H1-34_H1-34") (pintype "passive"))
      (node (ref "PC11") (pin "H1-34") (pinfunction "H1-34_H1-34") (pintype "passive"))
      (node (ref "PC4") (pin "H1-34") (pinfunction "H1-34_H1-34") (pintype "passive"))
      (node (ref "PC6") (pin "H1-34") (pinfunction "H1-34_H1-34") (pintype "passive"))
      (node (ref "PC8") (pin "H1-34") (pinfunction "H1-34_H1-34") (pintype "passive"))
      (node (ref "PC9") (pin "H1-34") (pinfunction "H1-34_H1-34") (pintype "passive"))
    )
    (net (code "41") (name "/H1-35") (class "Default")
      (node (ref "CN11") (pin "H1-35") (pinfunction "H1-35_H1-35") (pintype "passive"))
      (node (ref "PC1") (pin "H1-35") (pinfunction "H1-35_H1-35") (pintype "passive"))
      (node (ref "PC11") (pin "H1-35") (pinfunction "H1-35_H1-35") (pintype "passive"))
      (node (ref "PC4") (pin "H1-35") (pinfunction "H1-35_H1-35") (pintype "passive"))
      (node (ref "PC6") (pin "H1-35") (pinfunction "H1-35_H1-35") (pintype "passive"))
      (node (ref "PC8") (pin "H1-35") (pinfunction "H1-35_H1-35") (pintype "passive"))
      (node (ref "PC9") (pin "H1-35") (pinfunction "H1-35_H1-35") (pintype "passive"))
    )
    (net (code "42") (name "/H1-36") (class "Default")
      (node (ref "CN11") (pin "H1-36") (pinfunction "H1-36_H1-36") (pintype "passive"))
      (node (ref "PC1") (pin "H1-36") (pinfunction "H1-36_H1-36") (pintype "passive"))
      (node (ref "PC11") (pin "H1-36") (pinfunction "H1-36_H1-36") (pintype "passive"))
      (node (ref "PC4") (pin "H1-36") (pinfunction "H1-36_H1-36") (pintype "passive"))
      (node (ref "PC6") (pin "H1-36") (pinfunction "H1-36_H1-36") (pintype "passive"))
      (node (ref "PC8") (pin "H1-36") (pinfunction "H1-36_H1-36") (pintype "passive"))
      (node (ref "PC9") (pin "H1-36") (pinfunction "H1-36_H1-36") (pintype "passive"))
    )
    (net (code "43") (name "/H1-37") (class "Default")
      (node (ref "CN11") (pin "H1-37") (pinfunction "H1-37_H1-37") (pintype "passive"))
      (node (ref "PC1") (pin "H1-37") (pinfunction "H1-37_H1-37") (pintype "passive"))
      (node (ref "PC11") (pin "H1-37") (pinfunction "H1-37_H1-37") (pintype "passive"))
      (node (ref "PC4") (pin "H1-37") (pinfunction "H1-37_H1-37") (pintype "passive"))
      (node (ref "PC6") (pin "H1-37") (pinfunction "H1-37_H1-37") (pintype "passive"))
      (node (ref "PC8") (pin "H1-37") (pinfunction "H1-37_H1-37") (pintype "passive"))
      (node (ref "PC9") (pin "H1-37") (pinfunction "H1-37_H1-37") (pintype "passive"))
    )
    (net (code "44") (name "/H1-38") (class "Default")
      (node (ref "CN11") (pin "H1-38") (pinfunction "H1-38_H1-38") (pintype "passive"))
      (node (ref "PC1") (pin "H1-38") (pinfunction "H1-38_H1-38") (pintype "passive"))
      (node (ref "PC11") (pin "H1-38") (pinfunction "H1-38_H1-38") (pintype "passive"))
      (node (ref "PC4") (pin "H1-38") (pinfunction "H1-38_H1-38") (pintype "passive"))
      (node (ref "PC6") (pin "H1-38") (pinfunction "H1-38_H1-38") (pintype "passive"))
      (node (ref "PC8") (pin "H1-38") (pinfunction "H1-38_H1-38") (pintype "passive"))
      (node (ref "PC9") (pin "H1-38") (pinfunction "H1-38_H1-38") (pintype "passive"))
    )
    (net (code "45") (name "/H1-39") (class "Default")
      (node (ref "CN11") (pin "H1-39") (pinfunction "H1-39_H1-39") (pintype "passive"))
      (node (ref "PC1") (pin "H1-39") (pinfunction "H1-39_H1-39") (pintype "passive"))
      (node (ref "PC11") (pin "H1-39") (pinfunction "H1-39_H1-39") (pintype "passive"))
      (node (ref "PC4") (pin "H1-39") (pinfunction "H1-39_H1-39") (pintype "passive"))
      (node (ref "PC6") (pin "H1-39") (pinfunction "H1-39_H1-39") (pintype "passive"))
      (node (ref "PC8") (pin "H1-39") (pinfunction "H1-39_H1-39") (pintype "passive"))
      (node (ref "PC9") (pin "H1-39") (pinfunction "H1-39_H1-39") (pintype "passive"))
    )
    (net (code "46") (name "/H1-40") (class "Default")
      (node (ref "CN11") (pin "H1-40") (pinfunction "H1-40_H1-40") (pintype "passive"))
      (node (ref "PC1") (pin "H1-40") (pinfunction "H1-40_H1-40") (pintype "passive"))
      (node (ref "PC11") (pin "H1-40") (pinfunction "H1-40_H1-40") (pintype "passive"))
      (node (ref "PC4") (pin "H1-40") (pinfunction "H1-40_H1-40") (pintype "passive"))
      (node (ref "PC6") (pin "H1-40") (pinfunction "H1-40_H1-40") (pintype "passive"))
      (node (ref "PC8") (pin "H1-40") (pinfunction "H1-40_H1-40") (pintype "passive"))
      (node (ref "PC9") (pin "H1-40") (pinfunction "H1-40_H1-40") (pintype "passive"))
    )
    (net (code "47") (name "/H1-41") (class "Default")
      (node (ref "CN11") (pin "H1-41") (pinfunction "H1-41_H1-41") (pintype "passive"))
      (node (ref "PC1") (pin "H1-41") (pinfunction "H1-41_H1-41") (pintype "passive"))
      (node (ref "PC11") (pin "H1-41") (pinfunction "H1-41_H1-41") (pintype "passive"))
      (node (ref "PC4") (pin "H1-41") (pinfunction "H1-41_H1-41") (pintype "passive"))
      (node (ref "PC6") (pin "H1-41") (pinfunction "H1-41_H1-41") (pintype "passive"))
      (node (ref "PC8") (pin "H1-41") (pinfunction "H1-41_H1-41") (pintype "passive"))
      (node (ref "PC9") (pin "H1-41") (pinfunction "H1-41_H1-41") (pintype "passive"))
    )
    (net (code "48") (name "/H1-42") (class "Default")
      (node (ref "CN11") (pin "H1-42") (pinfunction "H1-42_H1-42") (pintype "passive"))
      (node (ref "PC1") (pin "H1-42") (pinfunction "H1-42_H1-42") (pintype "passive"))
      (node (ref "PC11") (pin "H1-42") (pinfunction "H1-42_H1-42") (pintype "passive"))
      (node (ref "PC4") (pin "H1-42") (pinfunction "H1-42_H1-42") (pintype "passive"))
      (node (ref "PC6") (pin "H1-42") (pinfunction "H1-42_H1-42") (pintype "passive"))
      (node (ref "PC8") (pin "H1-42") (pinfunction "H1-42_H1-42") (pintype "passive"))
      (node (ref "PC9") (pin "H1-42") (pinfunction "H1-42_H1-42") (pintype "passive"))
    )
    (net (code "49") (name "/H1-43") (class "Default")
      (node (ref "CN11") (pin "H1-43") (pinfunction "H1-43_H1-43") (pintype "passive"))
      (node (ref "PC1") (pin "H1-43") (pinfunction "H1-43_H1-43") (pintype "passive"))
      (node (ref "PC11") (pin "H1-43") (pinfunction "H1-43_H1-43") (pintype "passive"))
      (node (ref "PC4") (pin "H1-43") (pinfunction "H1-43_H1-43") (pintype "passive"))
      (node (ref "PC6") (pin "H1-43") (pinfunction "H1-43_H1-43") (pintype "passive"))
      (node (ref "PC8") (pin "H1-43") (pinfunction "H1-43_H1-43") (pintype "passive"))
      (node (ref "PC9") (pin "H1-43") (pinfunction "H1-43_H1-43") (pintype "passive"))
    )
    (net (code "50") (name "/H1-44") (class "Default")
      (node (ref "CN11") (pin "H1-44") (pinfunction "H1-44_H1-44") (pintype "passive"))
      (node (ref "PC1") (pin "H1-44") (pinfunction "H1-44_H1-44") (pintype "passive"))
      (node (ref "PC11") (pin "H1-44") (pinfunction "H1-44_H1-44") (pintype "passive"))
      (node (ref "PC4") (pin "H1-44") (pinfunction "H1-44_H1-44") (pintype "passive"))
      (node (ref "PC6") (pin "H1-44") (pinfunction "H1-44_H1-44") (pintype "passive"))
      (node (ref "PC8") (pin "H1-44") (pinfunction "H1-44_H1-44") (pintype "passive"))
      (node (ref "PC9") (pin "H1-44") (pinfunction "H1-44_H1-44") (pintype "passive"))
    )
    (net (code "51") (name "/H1-45") (class "Default")
      (node (ref "CN11") (pin "H1-45") (pinfunction "H1-45_H1-45") (pintype "passive"))
      (node (ref "PC1") (pin "H1-45") (pinfunction "H1-45_H1-45") (pintype "passive"))
      (node (ref "PC11") (pin "H1-45") (pinfunction "H1-45_H1-45") (pintype "passive"))
      (node (ref "PC4") (pin "H1-45") (pinfunction "H1-45_H1-45") (pintype "passive"))
      (node (ref "PC6") (pin "H1-45") (pinfunction "H1-45_H1-45") (pintype "passive"))
      (node (ref "PC8") (pin "H1-45") (pinfunction "H1-45_H1-45") (pintype "passive"))
      (node (ref "PC9") (pin "H1-45") (pinfunction "H1-45_H1-45") (pintype "passive"))
    )
    (net (code "52") (name "/H1-46") (class "Default")
      (node (ref "CN11") (pin "H1-46") (pinfunction "H1-46_H1-46") (pintype "passive"))
      (node (ref "PC1") (pin "H1-46") (pinfunction "H1-46_H1-46") (pintype "passive"))
      (node (ref "PC11") (pin "H1-46") (pinfunction "H1-46_H1-46") (pintype "passive"))
      (node (ref "PC4") (pin "H1-46") (pinfunction "H1-46_H1-46") (pintype "passive"))
      (node (ref "PC6") (pin "H1-46") (pinfunction "H1-46_H1-46") (pintype "passive"))
      (node (ref "PC8") (pin "H1-46") (pinfunction "H1-46_H1-46") (pintype "passive"))
      (node (ref "PC9") (pin "H1-46") (pinfunction "H1-46_H1-46") (pintype "passive"))
    )
    (net (code "53") (name "/H1-47") (class "Default")
      (node (ref "CN11") (pin "H1-47") (pinfunction "H1-47_H1-47") (pintype "passive"))
      (node (ref "PC1") (pin "H1-47") (pinfunction "H1-47_H1-47") (pintype "passive"))
      (node (ref "PC11") (pin "H1-47") (pinfunction "H1-47_H1-47") (pintype "passive"))
      (node (ref "PC4") (pin "H1-47") (pinfunction "H1-47_H1-47") (pintype "passive"))
      (node (ref "PC6") (pin "H1-47") (pinfunction "H1-47_H1-47") (pintype "passive"))
      (node (ref "PC8") (pin "H1-47") (pinfunction "H1-47_H1-47") (pintype "passive"))
      (node (ref "PC9") (pin "H1-47") (pinfunction "H1-47_H1-47") (pintype "passive"))
    )
    (net (code "54") (name "/H1-48") (class "Default")
      (node (ref "CN11") (pin "H1-48") (pinfunction "H1-48_H1-48") (pintype "passive"))
      (node (ref "PC1") (pin "H1-48") (pinfunction "H1-48_H1-48") (pintype "passive"))
      (node (ref "PC11") (pin "H1-48") (pinfunction "H1-48_H1-48") (pintype "passive"))
      (node (ref "PC4") (pin "H1-48") (pinfunction "H1-48_H1-48") (pintype "passive"))
      (node (ref "PC6") (pin "H1-48") (pinfunction "H1-48_H1-48") (pintype "passive"))
      (node (ref "PC8") (pin "H1-48") (pinfunction "H1-48_H1-48") (pintype "passive"))
      (node (ref "PC9") (pin "H1-48") (pinfunction "H1-48_H1-48") (pintype "passive"))
    )
    (net (code "55") (name "/H1-49") (class "Default")
      (node (ref "CN11") (pin "H1-49") (pinfunction "H1-49_H1-49") (pintype "passive"))
      (node (ref "PC1") (pin "H1-49") (pinfunction "H1-49_H1-49") (pintype "passive"))
      (node (ref "PC11") (pin "H1-49") (pinfunction "H1-49_H1-49") (pintype "passive"))
      (node (ref "PC4") (pin "H1-49") (pinfunction "H1-49_H1-49") (pintype "passive"))
      (node (ref "PC6") (pin "H1-49") (pinfunction "H1-49_H1-49") (pintype "passive"))
      (node (ref "PC8") (pin "H1-49") (pinfunction "H1-49_H1-49") (pintype "passive"))
      (node (ref "PC9") (pin "H1-49") (pinfunction "H1-49_H1-49") (pintype "passive"))
    )
    (net (code "56") (name "/H1-50") (class "Default")
      (node (ref "CN11") (pin "H1-50") (pinfunction "H1-50_H1-50") (pintype "passive"))
      (node (ref "PC1") (pin "H1-50") (pinfunction "H1-50_H1-50") (pintype "passive"))
      (node (ref "PC11") (pin "H1-50") (pinfunction "H1-50_H1-50") (pintype "passive"))
      (node (ref "PC4") (pin "H1-50") (pinfunction "H1-50_H1-50") (pintype "passive"))
      (node (ref "PC6") (pin "H1-50") (pinfunction "H1-50_H1-50") (pintype "passive"))
      (node (ref "PC8") (pin "H1-50") (pinfunction "H1-50_H1-50") (pintype "passive"))
      (node (ref "PC9") (pin "H1-50") (pinfunction "H1-50_H1-50") (pintype "passive"))
    )
    (net (code "57") (name "/H1-51") (class "Default")
      (node (ref "CN11") (pin "H1-51") (pinfunction "H1-51_H1-51") (pintype "passive"))
      (node (ref "PC1") (pin "H1-51") (pinfunction "H1-51_H1-51") (pintype "passive"))
      (node (ref "PC11") (pin "H1-51") (pinfunction "H1-51_H1-51") (pintype "passive"))
      (node (ref "PC4") (pin "H1-51") (pinfunction "H1-51_H1-51") (pintype "passive"))
      (node (ref "PC6") (pin "H1-51") (pinfunction "H1-51_H1-51") (pintype "passive"))
      (node (ref "PC8") (pin "H1-51") (pinfunction "H1-51_H1-51") (pintype "passive"))
      (node (ref "PC9") (pin "H1-51") (pinfunction "H1-51_H1-51") (pintype "passive"))
    )
    (net (code "58") (name "/H1-52") (class "Default")
      (node (ref "CN11") (pin "H1-52") (pinfunction "H1-52_H1-52") (pintype "passive"))
      (node (ref "PC1") (pin "H1-52") (pinfunction "H1-52_H1-52") (pintype "passive"))
      (node (ref "PC11") (pin "H1-52") (pinfunction "H1-52_H1-52") (pintype "passive"))
      (node (ref "PC4") (pin "H1-52") (pinfunction "H1-52_H1-52") (pintype "passive"))
      (node (ref "PC6") (pin "H1-52") (pinfunction "H1-52_H1-52") (pintype "passive"))
      (node (ref "PC8") (pin "H1-52") (pinfunction "H1-52_H1-52") (pintype "passive"))
      (node (ref "PC9") (pin "H1-52") (pinfunction "H1-52_H1-52") (pintype "passive"))
    )
    (net (code "59") (name "/H2-1") (class "Default")
      (node (ref "CN12") (pin "H2-1") (pinfunction "H2-1_H2-1") (pintype "passive"))
      (node (ref "PC10") (pin "H2-1") (pinfunction "H2-1_H2-1") (pintype "passive"))
      (node (ref "PC12") (pin "H2-1") (pinfunction "H2-1_H2-1") (pintype "passive"))
      (node (ref "PC2") (pin "H2-1") (pinfunction "H2-1_H2-1") (pintype "passive"))
      (node (ref "PC3") (pin "H2-1") (pinfunction "H2-1_H2-1") (pintype "passive"))
      (node (ref "PC5") (pin "H2-1") (pinfunction "H2-1_H2-1") (pintype "passive"))
      (node (ref "PC7") (pin "H2-1") (pinfunction "H2-1_H2-1") (pintype "passive"))
    )
    (net (code "60") (name "/H2-2") (class "Default")
      (node (ref "CN12") (pin "H2-2") (pinfunction "H2-2_H2-2") (pintype "passive"))
      (node (ref "PC10") (pin "H2-2") (pinfunction "H2-2_H2-2") (pintype "passive"))
      (node (ref "PC12") (pin "H2-2") (pinfunction "H2-2_H2-2") (pintype "passive"))
      (node (ref "PC2") (pin "H2-2") (pinfunction "H2-2_H2-2") (pintype "passive"))
      (node (ref "PC3") (pin "H2-2") (pinfunction "H2-2_H2-2") (pintype "passive"))
      (node (ref "PC5") (pin "H2-2") (pinfunction "H2-2_H2-2") (pintype "passive"))
      (node (ref "PC7") (pin "H2-2") (pinfunction "H2-2_H2-2") (pintype "passive"))
    )
    (net (code "61") (name "/H2-3") (class "Default")
      (node (ref "CN12") (pin "H2-3") (pinfunction "H2-3_H2-3") (pintype "passive"))
      (node (ref "PC10") (pin "H2-3") (pinfunction "H2-3_H2-3") (pintype "passive"))
      (node (ref "PC12") (pin "H2-3") (pinfunction "H2-3_H2-3") (pintype "passive"))
      (node (ref "PC2") (pin "H2-3") (pinfunction "H2-3_H2-3") (pintype "passive"))
      (node (ref "PC3") (pin "H2-3") (pinfunction "H2-3_H2-3") (pintype "passive"))
      (node (ref "PC5") (pin "H2-3") (pinfunction "H2-3_H2-3") (pintype "passive"))
      (node (ref "PC7") (pin "H2-3") (pinfunction "H2-3_H2-3") (pintype "passive"))
    )
    (net (code "62") (name "/H2-4") (class "Default")
      (node (ref "CN12") (pin "H2-4") (pinfunction "H2-4_H2-4") (pintype "passive"))
      (node (ref "PC10") (pin "H2-4") (pinfunction "H2-4_H2-4") (pintype "passive"))
      (node (ref "PC12") (pin "H2-4") (pinfunction "H2-4_H2-4") (pintype "passive"))
      (node (ref "PC2") (pin "H2-4") (pinfunction "H2-4_H2-4") (pintype "passive"))
      (node (ref "PC3") (pin "H2-4") (pinfunction "H2-4_H2-4") (pintype "passive"))
      (node (ref "PC5") (pin "H2-4") (pinfunction "H2-4_H2-4") (pintype "passive"))
      (node (ref "PC7") (pin "H2-4") (pinfunction "H2-4_H2-4") (pintype "passive"))
    )
    (net (code "63") (name "/H2-5") (class "Default")
      (node (ref "CN12") (pin "H2-5") (pinfunction "H2-5_H2-5") (pintype "passive"))
      (node (ref "PC10") (pin "H2-5") (pinfunction "H2-5_H2-5") (pintype "passive"))
      (node (ref "PC12") (pin "H2-5") (pinfunction "H2-5_H2-5") (pintype "passive"))
      (node (ref "PC2") (pin "H2-5") (pinfunction "H2-5_H2-5") (pintype "passive"))
      (node (ref "PC3") (pin "H2-5") (pinfunction "H2-5_H2-5") (pintype "passive"))
      (node (ref "PC5") (pin "H2-5") (pinfunction "H2-5_H2-5") (pintype "passive"))
      (node (ref "PC7") (pin "H2-5") (pinfunction "H2-5_H2-5") (pintype "passive"))
    )
    (net (code "64") (name "/H2-6") (class "Default")
      (node (ref "CN12") (pin "H2-6") (pinfunction "H2-6_H2-6") (pintype "passive"))
      (node (ref "PC10") (pin "H2-6") (pinfunction "H2-6_H2-6") (pintype "passive"))
      (node (ref "PC12") (pin "H2-6") (pinfunction "H2-6_H2-6") (pintype "passive"))
      (node (ref "PC2") (pin "H2-6") (pinfunction "H2-6_H2-6") (pintype "passive"))
      (node (ref "PC3") (pin "H2-6") (pinfunction "H2-6_H2-6") (pintype "passive"))
      (node (ref "PC5") (pin "H2-6") (pinfunction "H2-6_H2-6") (pintype "passive"))
      (node (ref "PC7") (pin "H2-6") (pinfunction "H2-6_H2-6") (pintype "passive"))
    )
    (net (code "65") (name "/H2-7") (class "Default")
      (node (ref "CN12") (pin "H2-7") (pinfunction "H2-7_H2-7") (pintype "passive"))
      (node (ref "PC10") (pin "H2-7") (pinfunction "H2-7_H2-7") (pintype "passive"))
      (node (ref "PC12") (pin "H2-7") (pinfunction "H2-7_H2-7") (pintype "passive"))
      (node (ref "PC2") (pin "H2-7") (pinfunction "H2-7_H2-7") (pintype "passive"))
      (node (ref "PC3") (pin "H2-7") (pinfunction "H2-7_H2-7") (pintype "passive"))
      (node (ref "PC5") (pin "H2-7") (pinfunction "H2-7_H2-7") (pintype "passive"))
      (node (ref "PC7") (pin "H2-7") (pinfunction "H2-7_H2-7") (pintype "passive"))
    )
    (net (code "66") (name "/H2-8") (class "Default")
      (node (ref "CN12") (pin "H2-8") (pinfunction "H2-8_H2-8") (pintype "passive"))
      (node (ref "PC10") (pin "H2-8") (pinfunction "H2-8_H2-8") (pintype "passive"))
      (node (ref "PC12") (pin "H2-8") (pinfunction "H2-8_H2-8") (pintype "passive"))
      (node (ref "PC2") (pin "H2-8") (pinfunction "H2-8_H2-8") (pintype "passive"))
      (node (ref "PC3") (pin "H2-8") (pinfunction "H2-8_H2-8") (pintype "passive"))
      (node (ref "PC5") (pin "H2-8") (pinfunction "H2-8_H2-8") (pintype "passive"))
      (node (ref "PC7") (pin "H2-8") (pinfunction "H2-8_H2-8") (pintype "passive"))
    )
    (net (code "67") (name "/H2-9") (class "Default")
      (node (ref "CN12") (pin "H2-9") (pinfunction "H2-9_H2-9") (pintype "passive"))
      (node (ref "PC10") (pin "H2-9") (pinfunction "H2-9_H2-9") (pintype "passive"))
      (node (ref "PC12") (pin "H2-9") (pinfunction "H2-9_H2-9") (pintype "passive"))
      (node (ref "PC2") (pin "H2-9") (pinfunction "H2-9_H2-9") (pintype "passive"))
      (node (ref "PC3") (pin "H2-9") (pinfunction "H2-9_H2-9") (pintype "passive"))
      (node (ref "PC5") (pin "H2-9") (pinfunction "H2-9_H2-9") (pintype "passive"))
      (node (ref "PC7") (pin "H2-9") (pinfunction "H2-9_H2-9") (pintype "passive"))
    )
    (net (code "68") (name "/H2-10") (class "Default")
      (node (ref "CN12") (pin "H2-10") (pinfunction "H2-10_H2-10") (pintype "passive"))
      (node (ref "PC10") (pin "H2-10") (pinfunction "H2-10_H2-10") (pintype "passive"))
      (node (ref "PC12") (pin "H2-10") (pinfunction "H2-10_H2-10") (pintype "passive"))
      (node (ref "PC2") (pin "H2-10") (pinfunction "H2-10_H2-10") (pintype "passive"))
      (node (ref "PC3") (pin "H2-10") (pinfunction "H2-10_H2-10") (pintype "passive"))
      (node (ref "PC5") (pin "H2-10") (pinfunction "H2-10_H2-10") (pintype "passive"))
      (node (ref "PC7") (pin "H2-10") (pinfunction "H2-10_H2-10") (pintype "passive"))
    )
    (net (code "69") (name "/H2-11") (class "Default")
      (node (ref "CN12") (pin "H2-11") (pinfunction "H2-11_H2-11") (pintype "passive"))
      (node (ref "PC10") (pin "H2-11") (pinfunction "H2-11_H2-11") (pintype "passive"))
      (node (ref "PC12") (pin "H2-11") (pinfunction "H2-11_H2-11") (pintype "passive"))
      (node (ref "PC2") (pin "H2-11") (pinfunction "H2-11_H2-11") (pintype "passive"))
      (node (ref "PC3") (pin "H2-11") (pinfunction "H2-11_H2-11") (pintype "passive"))
      (node (ref "PC5") (pin "H2-11") (pinfunction "H2-11_H2-11") (pintype "passive"))
      (node (ref "PC7") (pin "H2-11") (pinfunction "H2-11_H2-11") (pintype "passive"))
    )
    (net (code "70") (name "/H2-12") (class "Default")
      (node (ref "CN12") (pin "H2-12") (pinfunction "H2-12_H2-12") (pintype "passive"))
      (node (ref "PC10") (pin "H2-12") (pinfunction "H2-12_H2-12") (pintype "passive"))
      (node (ref "PC12") (pin "H2-12") (pinfunction "H2-12_H2-12") (pintype "passive"))
      (node (ref "PC2") (pin "H2-12") (pinfunction "H2-12_H2-12") (pintype "passive"))
      (node (ref "PC3") (pin "H2-12") (pinfunction "H2-12_H2-12") (pintype "passive"))
      (node (ref "PC5") (pin "H2-12") (pinfunction "H2-12_H2-12") (pintype "passive"))
      (node (ref "PC7") (pin "H2-12") (pinfunction "H2-12_H2-12") (pintype "passive"))
    )
    (net (code "71") (name "/H2-13") (class "Default")
      (node (ref "CN12") (pin "H2-13") (pinfunction "H2-13_H2-13") (pintype "passive"))
      (node (ref "PC10") (pin "H2-13") (pinfunction "H2-13_H2-13") (pintype "passive"))
      (node (ref "PC12") (pin "H2-13") (pinfunction "H2-13_H2-13") (pintype "passive"))
      (node (ref "PC2") (pin "H2-13") (pinfunction "H2-13_H2-13") (pintype "passive"))
      (node (ref "PC3") (pin "H2-13") (pinfunction "H2-13_H2-13") (pintype "passive"))
      (node (ref "PC5") (pin "H2-13") (pinfunction "H2-13_H2-13") (pintype "passive"))
      (node (ref "PC7") (pin "H2-13") (pinfunction "H2-13_H2-13") (pintype "passive"))
    )
    (net (code "72") (name "/H2-14") (class "Default")
      (node (ref "CN12") (pin "H2-14") (pinfunction "H2-14_H2-14") (pintype "passive"))
      (node (ref "PC10") (pin "H2-14") (pinfunction "H2-14_H2-14") (pintype "passive"))
      (node (ref "PC12") (pin "H2-14") (pinfunction "H2-14_H2-14") (pintype "passive"))
      (node (ref "PC2") (pin "H2-14") (pinfunction "H2-14_H2-14") (pintype "passive"))
      (node (ref "PC3") (pin "H2-14") (pinfunction "H2-14_H2-14") (pintype "passive"))
      (node (ref "PC5") (pin "H2-14") (pinfunction "H2-14_H2-14") (pintype "passive"))
      (node (ref "PC7") (pin "H2-14") (pinfunction "H2-14_H2-14") (pintype "passive"))
    )
    (net (code "73") (name "/H2-15") (class "Default")
      (node (ref "CN12") (pin "H2-15") (pinfunction "H2-15_H2-15") (pintype "passive"))
      (node (ref "PC10") (pin "H2-15") (pinfunction "H2-15_H2-15") (pintype "passive"))
      (node (ref "PC12") (pin "H2-15") (pinfunction "H2-15_H2-15") (pintype "passive"))
      (node (ref "PC2") (pin "H2-15") (pinfunction "H2-15_H2-15") (pintype "passive"))
      (node (ref "PC3") (pin "H2-15") (pinfunction "H2-15_H2-15") (pintype "passive"))
      (node (ref "PC5") (pin "H2-15") (pinfunction "H2-15_H2-15") (pintype "passive"))
      (node (ref "PC7") (pin "H2-15") (pinfunction "H2-15_H2-15") (pintype "passive"))
    )
    (net (code "74") (name "/H2-16") (class "Default")
      (node (ref "CN12") (pin "H2-16") (pinfunction "H2-16_H2-16") (pintype "passive"))
      (node (ref "PC10") (pin "H2-16") (pinfunction "H2-16_H2-16") (pintype "passive"))
      (node (ref "PC12") (pin "H2-16") (pinfunction "H2-16_H2-16") (pintype "passive"))
      (node (ref "PC2") (pin "H2-16") (pinfunction "H2-16_H2-16") (pintype "passive"))
      (node (ref "PC3") (pin "H2-16") (pinfunction "H2-16_H2-16") (pintype "passive"))
      (node (ref "PC5") (pin "H2-16") (pinfunction "H2-16_H2-16") (pintype "passive"))
      (node (ref "PC7") (pin "H2-16") (pinfunction "H2-16_H2-16") (pintype "passive"))
    )
    (net (code "75") (name "/H2-17") (class "Default")
      (node (ref "CN12") (pin "H2-17") (pinfunction "H2-17_H2-17") (pintype "passive"))
      (node (ref "PC10") (pin "H2-17") (pinfunction "H2-17_H2-17") (pintype "passive"))
      (node (ref "PC12") (pin "H2-17") (pinfunction "H2-17_H2-17") (pintype "passive"))
      (node (ref "PC2") (pin "H2-17") (pinfunction "H2-17_H2-17") (pintype "passive"))
      (node (ref "PC3") (pin "H2-17") (pinfunction "H2-17_H2-17") (pintype "passive"))
      (node (ref "PC5") (pin "H2-17") (pinfunction "H2-17_H2-17") (pintype "passive"))
      (node (ref "PC7") (pin "H2-17") (pinfunction "H2-17_H2-17") (pintype "passive"))
    )
    (net (code "76") (name "/H2-18") (class "Default")
      (node (ref "CN12") (pin "H2-18") (pinfunction "H2-18_H2-18") (pintype "passive"))
      (node (ref "PC10") (pin "H2-18") (pinfunction "H2-18_H2-18") (pintype "passive"))
      (node (ref "PC12") (pin "H2-18") (pinfunction "H2-18_H2-18") (pintype "passive"))
      (node (ref "PC2") (pin "H2-18") (pinfunction "H2-18_H2-18") (pintype "passive"))
      (node (ref "PC3") (pin "H2-18") (pinfunction "H2-18_H2-18") (pintype "passive"))
      (node (ref "PC5") (pin "H2-18") (pinfunction "H2-18_H2-18") (pintype "passive"))
      (node (ref "PC7") (pin "H2-18") (pinfunction "H2-18_H2-18") (pintype "passive"))
    )
    (net (code "77") (name "/H2-19") (class "Default")
      (node (ref "CN12") (pin "H2-19") (pinfunction "H2-19_H2-19") (pintype "passive"))
      (node (ref "PC10") (pin "H2-19") (pinfunction "H2-19_H2-19") (pintype "passive"))
      (node (ref "PC12") (pin "H2-19") (pinfunction "H2-19_H2-19") (pintype "passive"))
      (node (ref "PC2") (pin "H2-19") (pinfunction "H2-19_H2-19") (pintype "passive"))
      (node (ref "PC3") (pin "H2-19") (pinfunction "H2-19_H2-19") (pintype "passive"))
      (node (ref "PC5") (pin "H2-19") (pinfunction "H2-19_H2-19") (pintype "passive"))
      (node (ref "PC7") (pin "H2-19") (pinfunction "H2-19_H2-19") (pintype "passive"))
    )
    (net (code "78") (name "/H2-20") (class "Default")
      (node (ref "CN12") (pin "H2-20") (pinfunction "H2-20_H2-20") (pintype "passive"))
      (node (ref "PC10") (pin "H2-20") (pinfunction "H2-20_H2-20") (pintype "passive"))
      (node (ref "PC12") (pin "H2-20") (pinfunction "H2-20_H2-20") (pintype "passive"))
      (node (ref "PC2") (pin "H2-20") (pinfunction "H2-20_H2-20") (pintype "passive"))
      (node (ref "PC3") (pin "H2-20") (pinfunction "H2-20_H2-20") (pintype "passive"))
      (node (ref "PC5") (pin "H2-20") (pinfunction "H2-20_H2-20") (pintype "passive"))
      (node (ref "PC7") (pin "H2-20") (pinfunction "H2-20_H2-20") (pintype "passive"))
    )
    (net (code "79") (name "/H2-21") (class "Default")
      (node (ref "CN12") (pin "H2-21") (pinfunction "H2-21_H2-21") (pintype "passive"))
      (node (ref "PC10") (pin "H2-21") (pinfunction "H2-21_H2-21") (pintype "passive"))
      (node (ref "PC12") (pin "H2-21") (pinfunction "H2-21_H2-21") (pintype "passive"))
      (node (ref "PC2") (pin "H2-21") (pinfunction "H2-21_H2-21") (pintype "passive"))
      (node (ref "PC3") (pin "H2-21") (pinfunction "H2-21_H2-21") (pintype "passive"))
      (node (ref "PC5") (pin "H2-21") (pinfunction "H2-21_H2-21") (pintype "passive"))
      (node (ref "PC7") (pin "H2-21") (pinfunction "H2-21_H2-21") (pintype "passive"))
    )
    (net (code "80") (name "/H2-22") (class "Default")
      (node (ref "CN12") (pin "H2-22") (pinfunction "H2-22_H2-22") (pintype "passive"))
      (node (ref "PC10") (pin "H2-22") (pinfunction "H2-22_H2-22") (pintype "passive"))
      (node (ref "PC12") (pin "H2-22") (pinfunction "H2-22_H2-22") (pintype "passive"))
      (node (ref "PC2") (pin "H2-22") (pinfunction "H2-22_H2-22") (pintype "passive"))
      (node (ref "PC3") (pin "H2-22") (pinfunction "H2-22_H2-22") (pintype "passive"))
      (node (ref "PC5") (pin "H2-22") (pinfunction "H2-22_H2-22") (pintype "passive"))
      (node (ref "PC7") (pin "H2-22") (pinfunction "H2-22_H2-22") (pintype "passive"))
    )
    (net (code "81") (name "/H2-23") (class "Default")
      (node (ref "CN12") (pin "H2-23") (pinfunction "H2-23_H2-23") (pintype "passive"))
      (node (ref "PC10") (pin "H2-23") (pinfunction "H2-23_H2-23") (pintype "passive"))
      (node (ref "PC12") (pin "H2-23") (pinfunction "H2-23_H2-23") (pintype "passive"))
      (node (ref "PC2") (pin "H2-23") (pinfunction "H2-23_H2-23") (pintype "passive"))
      (node (ref "PC3") (pin "H2-23") (pinfunction "H2-23_H2-23") (pintype "passive"))
      (node (ref "PC5") (pin "H2-23") (pinfunction "H2-23_H2-23") (pintype "passive"))
      (node (ref "PC7") (pin "H2-23") (pinfunction "H2-23_H2-23") (pintype "passive"))
    )
    (net (code "82") (name "/H2-24") (class "Default")
      (node (ref "CN12") (pin "H2-24") (pinfunction "H2-24_H2-24") (pintype "passive"))
      (node (ref "PC10") (pin "H2-24") (pinfunction "H2-24_H2-24") (pintype "passive"))
      (node (ref "PC12") (pin "H2-24") (pinfunction "H2-24_H2-24") (pintype "passive"))
      (node (ref "PC2") (pin "H2-24") (pinfunction "H2-24_H2-24") (pintype "passive"))
      (node (ref "PC3") (pin "H2-24") (pinfunction "H2-24_H2-24") (pintype "passive"))
      (node (ref "PC5") (pin "H2-24") (pinfunction "H2-24_H2-24") (pintype "passive"))
      (node (ref "PC7") (pin "H2-24") (pinfunction "H2-24_H2-24") (pintype "passive"))
    )
    (net (code "83") (name "/H2-25") (class "Default")
      (node (ref "CN12") (pin "H2-25") (pinfunction "H2-25_H2-25") (pintype "passive"))
      (node (ref "PC10") (pin "H2-25") (pinfunction "H2-25_H2-25") (pintype "passive"))
      (node (ref "PC12") (pin "H2-25") (pinfunction "H2-25_H2-25") (pintype "passive"))
      (node (ref "PC2") (pin "H2-25") (pinfunction "H2-25_H2-25") (pintype "passive"))
      (node (ref "PC3") (pin "H2-25") (pinfunction "H2-25_H2-25") (pintype "passive"))
      (node (ref "PC5") (pin "H2-25") (pinfunction "H2-25_H2-25") (pintype "passive"))
      (node (ref "PC7") (pin "H2-25") (pinfunction "H2-25_H2-25") (pintype "passive"))
    )
    (net (code "84") (name "/H2-26") (class "Default")
      (node (ref "CN12") (pin "H2-26") (pinfunction "H2-26_H2-26") (pintype "passive"))
      (node (ref "PC10") (pin "H2-26") (pinfunction "H2-26_H2-26") (pintype "passive"))
      (node (ref "PC12") (pin "H2-26") (pinfunction "H2-26_H2-26") (pintype "passive"))
      (node (ref "PC2") (pin "H2-26") (pinfunction "H2-26_H2-26") (pintype "passive"))
      (node (ref "PC3") (pin "H2-26") (pinfunction "H2-26_H2-26") (pintype "passive"))
      (node (ref "PC5") (pin "H2-26") (pinfunction "H2-26_H2-26") (pintype "passive"))
      (node (ref "PC7") (pin "H2-26") (pinfunction "H2-26_H2-26") (pintype "passive"))
    )
    (net (code "85") (name "/H2-27") (class "Default")
      (node (ref "CN12") (pin "H2-27") (pinfunction "H2-27_H2-27") (pintype "passive"))
      (node (ref "PC10") (pin "H2-27") (pinfunction "H2-27_H2-27") (pintype "passive"))
      (node (ref "PC12") (pin "H2-27") (pinfunction "H2-27_H2-27") (pintype "passive"))
      (node (ref "PC2") (pin "H2-27") (pinfunction "H2-27_H2-27") (pintype "passive"))
      (node (ref "PC3") (pin "H2-27") (pinfunction "H2-27_H2-27") (pintype "passive"))
      (node (ref "PC5") (pin "H2-27") (pinfunction "H2-27_H2-27") (pintype "passive"))
      (node (ref "PC7") (pin "H2-27") (pinfunction "H2-27_H2-27") (pintype "passive"))
    )
    (net (code "86") (name "/H2-28") (class "Default")
      (node (ref "CN12") (pin "H2-28") (pinfunction "H2-28_H2-28") (pintype "passive"))
      (node (ref "PC10") (pin "H2-28") (pinfunction "H2-28_H2-28") (pintype "passive"))
      (node (ref "PC12") (pin "H2-28") (pinfunction "H2-28_H2-28") (pintype "passive"))
      (node (ref "PC2") (pin "H2-28") (pinfunction "H2-28_H2-28") (pintype "passive"))
      (node (ref "PC3") (pin "H2-28") (pinfunction "H2-28_H2-28") (pintype "passive"))
      (node (ref "PC5") (pin "H2-28") (pinfunction "H2-28_H2-28") (pintype "passive"))
      (node (ref "PC7") (pin "H2-28") (pinfunction "H2-28_H2-28") (pintype "passive"))
    )
    (net (code "87") (name "/H2-29") (class "Default")
      (node (ref "CN12") (pin "H2-29") (pinfunction "H2-29_H2-29") (pintype "passive"))
      (node (ref "PC10") (pin "H2-29") (pinfunction "H2-29_H2-29") (pintype "passive"))
      (node (ref "PC12") (pin "H2-29") (pinfunction "H2-29_H2-29") (pintype "passive"))
      (node (ref "PC2") (pin "H2-29") (pinfunction "H2-29_H2-29") (pintype "passive"))
      (node (ref "PC3") (pin "H2-29") (pinfunction "H2-29_H2-29") (pintype "passive"))
      (node (ref "PC5") (pin "H2-29") (pinfunction "H2-29_H2-29") (pintype "passive"))
      (node (ref "PC7") (pin "H2-29") (pinfunction "H2-29_H2-29") (pintype "passive"))
    )
    (net (code "88") (name "/H2-30") (class "Default")
      (node (ref "CN12") (pin "H2-30") (pinfunction "H2-30_H2-30") (pintype "passive"))
      (node (ref "PC10") (pin "H2-30") (pinfunction "H2-30_H2-30") (pintype "passive"))
      (node (ref "PC12") (pin "H2-30") (pinfunction "H2-30_H2-30") (pintype "passive"))
      (node (ref "PC2") (pin "H2-30") (pinfunction "H2-30_H2-30") (pintype "passive"))
      (node (ref "PC3") (pin "H2-30") (pinfunction "H2-30_H2-30") (pintype "passive"))
      (node (ref "PC5") (pin "H2-30") (pinfunction "H2-30_H2-30") (pintype "passive"))
      (node (ref "PC7") (pin "H2-30") (pinfunction "H2-30_H2-30") (pintype "passive"))
    )
    (net (code "89") (name "/H2-31") (class "Default")
      (node (ref "CN12") (pin "H2-31") (pinfunction "H2-31_H2-31") (pintype "passive"))
      (node (ref "PC10") (pin "H2-31") (pinfunction "H2-31_H2-31") (pintype "passive"))
      (node (ref "PC12") (pin "H2-31") (pinfunction "H2-31_H2-31") (pintype "passive"))
      (node (ref "PC2") (pin "H2-31") (pinfunction "H2-31_H2-31") (pintype "passive"))
      (node (ref "PC3") (pin "H2-31") (pinfunction "H2-31_H2-31") (pintype "passive"))
      (node (ref "PC5") (pin "H2-31") (pinfunction "H2-31_H2-31") (pintype "passive"))
      (node (ref "PC7") (pin "H2-31") (pinfunction "H2-31_H2-31") (pintype "passive"))
    )
    (net (code "90") (name "/H2-32") (class "Default")
      (node (ref "CN12") (pin "H2-32") (pinfunction "H2-32_H2-32") (pintype "passive"))
      (node (ref "PC10") (pin "H2-32") (pinfunction "H2-32_H2-32") (pintype "passive"))
      (node (ref "PC12") (pin "H2-32") (pinfunction "H2-32_H2-32") (pintype "passive"))
      (node (ref "PC2") (pin "H2-32") (pinfunction "H2-32_H2-32") (pintype "passive"))
      (node (ref "PC3") (pin "H2-32") (pinfunction "H2-32_H2-32") (pintype "passive"))
      (node (ref "PC5") (pin "H2-32") (pinfunction "H2-32_H2-32") (pintype "passive"))
      (node (ref "PC7") (pin "H2-32") (pinfunction "H2-32_H2-32") (pintype "passive"))
    )
    (net (code "91") (name "/H2-33") (class "Default")
      (node (ref "CN12") (pin "H2-33") (pinfunction "H2-33_H2-33") (pintype "passive"))
      (node (ref "PC10") (pin "H2-33") (pinfunction "H2-33_H2-33") (pintype "passive"))
      (node (ref "PC12") (pin "H2-33") (pinfunction "H2-33_H2-33") (pintype "passive"))
      (node (ref "PC2") (pin "H2-33") (pinfunction "H2-33_H2-33") (pintype "passive"))
      (node (ref "PC3") (pin "H2-33") (pinfunction "H2-33_H2-33") (pintype "passive"))
      (node (ref "PC5") (pin "H2-33") (pinfunction "H2-33_H2-33") (pintype "passive"))
      (node (ref "PC7") (pin "H2-33") (pinfunction "H2-33_H2-33") (pintype "passive"))
    )
    (net (code "92") (name "/H2-34") (class "Default")
      (node (ref "CN12") (pin "H2-34") (pinfunction "H2-34_H2-34") (pintype "passive"))
      (node (ref "PC10") (pin "H2-34") (pinfunction "H2-34_H2-34") (pintype "passive"))
      (node (ref "PC12") (pin "H2-34") (pinfunction "H2-34_H2-34") (pintype "passive"))
      (node (ref "PC2") (pin "H2-34") (pinfunction "H2-34_H2-34") (pintype "passive"))
      (node (ref "PC3") (pin "H2-34") (pinfunction "H2-34_H2-34") (pintype "passive"))
      (node (ref "PC5") (pin "H2-34") (pinfunction "H2-34_H2-34") (pintype "passive"))
      (node (ref "PC7") (pin "H2-34") (pinfunction "H2-34_H2-34") (pintype "passive"))
    )
    (net (code "93") (name "/H2-35") (class "Default")
      (node (ref "CN12") (pin "H2-35") (pinfunction "H2-35_H2-35") (pintype "passive"))
      (node (ref "PC10") (pin "H2-35") (pinfunction "H2-35_H2-35") (pintype "passive"))
      (node (ref "PC12") (pin "H2-35") (pinfunction "H2-35_H2-35") (pintype "passive"))
      (node (ref "PC2") (pin "H2-35") (pinfunction "H2-35_H2-35") (pintype "passive"))
      (node (ref "PC3") (pin "H2-35") (pinfunction "H2-35_H2-35") (pintype "passive"))
      (node (ref "PC5") (pin "H2-35") (pinfunction "H2-35_H2-35") (pintype "passive"))
      (node (ref "PC7") (pin "H2-35") (pinfunction "H2-35_H2-35") (pintype "passive"))
    )
    (net (code "94") (name "/H2-36") (class "Default")
      (node (ref "CN12") (pin "H2-36") (pinfunction "H2-36_H2-36") (pintype "passive"))
      (node (ref "PC10") (pin "H2-36") (pinfunction "H2-36_H2-36") (pintype "passive"))
      (node (ref "PC12") (pin "H2-36") (pinfunction "H2-36_H2-36") (pintype "passive"))
      (node (ref "PC2") (pin "H2-36") (pinfunction "H2-36_H2-36") (pintype "passive"))
      (node (ref "PC3") (pin "H2-36") (pinfunction "H2-36_H2-36") (pintype "passive"))
      (node (ref "PC5") (pin "H2-36") (pinfunction "H2-36_H2-36") (pintype "passive"))
      (node (ref "PC7") (pin "H2-36") (pinfunction "H2-36_H2-36") (pintype "passive"))
    )
    (net (code "95") (name "/H2-37") (class "Default")
      (node (ref "CN12") (pin "H2-37") (pinfunction "H2-37_H2-37") (pintype "passive"))
      (node (ref "PC10") (pin "H2-37") (pinfunction "H2-37_H2-37") (pintype "passive"))
      (node (ref "PC12") (pin "H2-37") (pinfunction "H2-37_H2-37") (pintype "passive"))
      (node (ref "PC2") (pin "H2-37") (pinfunction "H2-37_H2-37") (pintype "passive"))
      (node (ref "PC3") (pin "H2-37") (pinfunction "H2-37_H2-37") (pintype "passive"))
      (node (ref "PC5") (pin "H2-37") (pinfunction "H2-37_H2-37") (pintype "passive"))
      (node (ref "PC7") (pin "H2-37") (pinfunction "H2-37_H2-37") (pintype "passive"))
    )
    (net (code "96") (name "/H2-38") (class "Default")
      (node (ref "CN12") (pin "H2-38") (pinfunction "H2-38_H2-38") (pintype "passive"))
      (node (ref "PC10") (pin "H2-38") (pinfunction "H2-38_H2-38") (pintype "passive"))
      (node (ref "PC12") (pin "H2-38") (pinfunction "H2-38_H2-38") (pintype "passive"))
      (node (ref "PC2") (pin "H2-38") (pinfunction "H2-38_H2-38") (pintype "passive"))
      (node (ref "PC3") (pin "H2-38") (pinfunction "H2-38_H2-38") (pintype "passive"))
      (node (ref "PC5") (pin "H2-38") (pinfunction "H2-38_H2-38") (pintype "passive"))
      (node (ref "PC7") (pin "H2-38") (pinfunction "H2-38_H2-38") (pintype "passive"))
    )
    (net (code "97") (name "/H2-39") (class "Default")
      (node (ref "CN12") (pin "H2-39") (pinfunction "H2-39_H2-39") (pintype "passive"))
      (node (ref "PC10") (pin "H2-39") (pinfunction "H2-39_H2-39") (pintype "passive"))
      (node (ref "PC12") (pin "H2-39") (pinfunction "H2-39_H2-39") (pintype "passive"))
      (node (ref "PC2") (pin "H2-39") (pinfunction "H2-39_H2-39") (pintype "passive"))
      (node (ref "PC3") (pin "H2-39") (pinfunction "H2-39_H2-39") (pintype "passive"))
      (node (ref "PC5") (pin "H2-39") (pinfunction "H2-39_H2-39") (pintype "passive"))
      (node (ref "PC7") (pin "H2-39") (pinfunction "H2-39_H2-39") (pintype "passive"))
    )
    (net (code "98") (name "/H2-40") (class "Default")
      (node (ref "CN12") (pin "H2-40") (pinfunction "H2-40_H2-40") (pintype "passive"))
      (node (ref "PC10") (pin "H2-40") (pinfunction "H2-40_H2-40") (pintype "passive"))
      (node (ref "PC12") (pin "H2-40") (pinfunction "H2-40_H2-40") (pintype "passive"))
      (node (ref "PC2") (pin "H2-40") (pinfunction "H2-40_H2-40") (pintype "passive"))
      (node (ref "PC3") (pin "H2-40") (pinfunction "H2-40_H2-40") (pintype "passive"))
      (node (ref "PC5") (pin "H2-40") (pinfunction "H2-40_H2-40") (pintype "passive"))
      (node (ref "PC7") (pin "H2-40") (pinfunction "H2-40_H2-40") (pintype "passive"))
    )
    (net (code "99") (name "/H2-41") (class "Default")
      (node (ref "CN12") (pin "H2-41") (pinfunction "H2-41_H2-41") (pintype "passive"))
      (node (ref "PC10") (pin "H2-41") (pinfunction "H2-41_H2-41") (pintype "passive"))
      (node (ref "PC12") (pin "H2-41") (pinfunction "H2-41_H2-41") (pintype "passive"))
      (node (ref "PC2") (pin "H2-41") (pinfunction "H2-41_H2-41") (pintype "passive"))
      (node (ref "PC3") (pin "H2-41") (pinfunction "H2-41_H2-41") (pintype "passive"))
      (node (ref "PC5") (pin "H2-41") (pinfunction "H2-41_H2-41") (pintype "passive"))
      (node (ref "PC7") (pin "H2-41") (pinfunction "H2-41_H2-41") (pintype "passive"))
    )
    (net (code "100") (name "/H2-42") (class "Default")
      (node (ref "CN12") (pin "H2-42") (pinfunction "H2-42_H2-42") (pintype "passive"))
      (node (ref "PC10") (pin "H2-42") (pinfunction "H2-42_H2-42") (pintype "passive"))
      (node (ref "PC12") (pin "H2-42") (pinfunction "H2-42_H2-42") (pintype "passive"))
      (node (ref "PC2") (pin "H2-42") (pinfunction "H2-42_H2-42") (pintype "passive"))
      (node (ref "PC3") (pin "H2-42") (pinfunction "H2-42_H2-42") (pintype "passive"))
      (node (ref "PC5") (pin "H2-42") (pinfunction "H2-42_H2-42") (pintype "passive"))
      (node (ref "PC7") (pin "H2-42") (pinfunction "H2-42_H2-42") (pintype "passive"))
    )
    (net (code "101") (name "/H2-43") (class "Default")
      (node (ref "CN12") (pin "H2-43") (pinfunction "H2-43_H2-43") (pintype "passive"))
      (node (ref "PC10") (pin "H2-43") (pinfunction "H2-43_H2-43") (pintype "passive"))
      (node (ref "PC12") (pin "H2-43") (pinfunction "H2-43_H2-43") (pintype "passive"))
      (node (ref "PC2") (pin "H2-43") (pinfunction "H2-43_H2-43") (pintype "passive"))
      (node (ref "PC3") (pin "H2-43") (pinfunction "H2-43_H2-43") (pintype "passive"))
      (node (ref "PC5") (pin "H2-43") (pinfunction "H2-43_H2-43") (pintype "passive"))
      (node (ref "PC7") (pin "H2-43") (pinfunction "H2-43_H2-43") (pintype "passive"))
    )
    (net (code "102") (name "/H2-44") (class "Default")
      (node (ref "CN12") (pin "H2-44") (pinfunction "H2-44_H2-44") (pintype "passive"))
      (node (ref "PC10") (pin "H2-44") (pinfunction "H2-44_H2-44") (pintype "passive"))
      (node (ref "PC12") (pin "H2-44") (pinfunction "H2-44_H2-44") (pintype "passive"))
      (node (ref "PC2") (pin "H2-44") (pinfunction "H2-44_H2-44") (pintype "passive"))
      (node (ref "PC3") (pin "H2-44") (pinfunction "H2-44_H2-44") (pintype "passive"))
      (node (ref "PC5") (pin "H2-44") (pinfunction "H2-44_H2-44") (pintype "passive"))
      (node (ref "PC7") (pin "H2-44") (pinfunction "H2-44_H2-44") (pintype "passive"))
    )
    (net (code "103") (name "/H2-45") (class "Default")
      (node (ref "CN12") (pin "H2-45") (pinfunction "H2-45_H2-45") (pintype "passive"))
      (node (ref "PC10") (pin "H2-45") (pinfunction "H2-45_H2-45") (pintype "passive"))
      (node (ref "PC12") (pin "H2-45") (pinfunction "H2-45_H2-45") (pintype "passive"))
      (node (ref "PC2") (pin "H2-45") (pinfunction "H2-45_H2-45") (pintype "passive"))
      (node (ref "PC3") (pin "H2-45") (pinfunction "H2-45_H2-45") (pintype "passive"))
      (node (ref "PC5") (pin "H2-45") (pinfunction "H2-45_H2-45") (pintype "passive"))
      (node (ref "PC7") (pin "H2-45") (pinfunction "H2-45_H2-45") (pintype "passive"))
    )
    (net (code "104") (name "/H2-46") (class "Default")
      (node (ref "CN12") (pin "H2-46") (pinfunction "H2-46_H2-46") (pintype "passive"))
      (node (ref "PC10") (pin "H2-46") (pinfunction "H2-46_H2-46") (pintype "passive"))
      (node (ref "PC12") (pin "H2-46") (pinfunction "H2-46_H2-46") (pintype "passive"))
      (node (ref "PC2") (pin "H2-46") (pinfunction "H2-46_H2-46") (pintype "passive"))
      (node (ref "PC3") (pin "H2-46") (pinfunction "H2-46_H2-46") (pintype "passive"))
      (node (ref "PC5") (pin "H2-46") (pinfunction "H2-46_H2-46") (pintype "passive"))
      (node (ref "PC7") (pin "H2-46") (pinfunction "H2-46_H2-46") (pintype "passive"))
    )
    (net (code "105") (name "/H2-47") (class "Default")
      (node (ref "CN12") (pin "H2-47") (pinfunction "H2-47_H2-47") (pintype "passive"))
      (node (ref "PC10") (pin "H2-47") (pinfunction "H2-47_H2-47") (pintype "passive"))
      (node (ref "PC12") (pin "H2-47") (pinfunction "H2-47_H2-47") (pintype "passive"))
      (node (ref "PC2") (pin "H2-47") (pinfunction "H2-47_H2-47") (pintype "passive"))
      (node (ref "PC3") (pin "H2-47") (pinfunction "H2-47_H2-47") (pintype "passive"))
      (node (ref "PC5") (pin "H2-47") (pinfunction "H2-47_H2-47") (pintype "passive"))
      (node (ref "PC7") (pin "H2-47") (pinfunction "H2-47_H2-47") (pintype "passive"))
    )
    (net (code "106") (name "/H2-48") (class "Default")
      (node (ref "CN12") (pin "H2-48") (pinfunction "H2-48_H2-48") (pintype "passive"))
      (node (ref "PC10") (pin "H2-48") (pinfunction "H2-48_H2-48") (pintype "passive"))
      (node (ref "PC12") (pin "H2-48") (pinfunction "H2-48_H2-48") (pintype "passive"))
      (node (ref "PC2") (pin "H2-48") (pinfunction "H2-48_H2-48") (pintype "passive"))
      (node (ref "PC3") (pin "H2-48") (pinfunction "H2-48_H2-48") (pintype "passive"))
      (node (ref "PC5") (pin "H2-48") (pinfunction "H2-48_H2-48") (pintype "passive"))
      (node (ref "PC7") (pin "H2-48") (pinfunction "H2-48_H2-48") (pintype "passive"))
    )
    (net (code "107") (name "/H2-49") (class "Default")
      (node (ref "CN12") (pin "H2-49") (pinfunction "H2-49_H2-49") (pintype "passive"))
      (node (ref "PC10") (pin "H2-49") (pinfunction "H2-49_H2-49") (pintype "passive"))
      (node (ref "PC12") (pin "H2-49") (pinfunction "H2-49_H2-49") (pintype "passive"))
      (node (ref "PC2") (pin "H2-49") (pinfunction "H2-49_H2-49") (pintype "passive"))
      (node (ref "PC3") (pin "H2-49") (pinfunction "H2-49_H2-49") (pintype "passive"))
      (node (ref "PC5") (pin "H2-49") (pinfunction "H2-49_H2-49") (pintype "passive"))
      (node (ref "PC7") (pin "H2-49") (pinfunction "H2-49_H2-49") (pintype "passive"))
    )
    (net (code "108") (name "/H2-50") (class "Default")
      (node (ref "CN12") (pin "H2-50") (pinfunction "H2-50_H2-50") (pintype "passive"))
      (node (ref "PC10") (pin "H2-50") (pinfunction "H2-50_H2-50") (pintype "passive"))
      (node (ref "PC12") (pin "H2-50") (pinfunction "H2-50_H2-50") (pintype "passive"))
      (node (ref "PC2") (pin "H2-50") (pinfunction "H2-50_H2-50") (pintype "passive"))
      (node (ref "PC3") (pin "H2-50") (pinfunction "H2-50_H2-50") (pintype "passive"))
      (node (ref "PC5") (pin "H2-50") (pinfunction "H2-50_H2-50") (pintype "passive"))
      (node (ref "PC7") (pin "H2-50") (pinfunction "H2-50_H2-50") (pintype "passive"))
    )
    (net (code "109") (name "/H2-51") (class "Default")
      (node (ref "CN12") (pin "H2-51") (pinfunction "H2-51_H2-51") (pintype "passive"))
      (node (ref "PC10") (pin "H2-51") (pinfunction "H2-51_H2-51") (pintype "passive"))
      (node (ref "PC12") (pin "H2-51") (pinfunction "H2-51_H2-51") (pintype "passive"))
      (node (ref "PC2") (pin "H2-51") (pinfunction "H2-51_H2-51") (pintype "passive"))
      (node (ref "PC3") (pin "H2-51") (pinfunction "H2-51_H2-51") (pintype "passive"))
      (node (ref "PC5") (pin "H2-51") (pinfunction "H2-51_H2-51") (pintype "passive"))
      (node (ref "PC7") (pin "H2-51") (pinfunction "H2-51_H2-51") (pintype "passive"))
    )
    (net (code "110") (name "/H2-52") (class "Default")
      (node (ref "CN12") (pin "H2-52") (pinfunction "H2-52_H2-52") (pintype "passive"))
      (node (ref "PC10") (pin "H2-52") (pinfunction "H2-52_H2-52") (pintype "passive"))
      (node (ref "PC12") (pin "H2-52") (pinfunction "H2-52_H2-52") (pintype "passive"))
      (node (ref "PC2") (pin "H2-52") (pinfunction "H2-52_H2-52") (pintype "passive"))
      (node (ref "PC3") (pin "H2-52") (pinfunction "H2-52_H2-52") (pintype "passive"))
      (node (ref "PC5") (pin "H2-52") (pinfunction "H2-52_H2-52") (pintype "passive"))
      (node (ref "PC7") (pin "H2-52") (pinfunction "H2-52_H2-52") (pintype "passive"))
    )
    (net (code "111") (name "/NC_Kill_Switch1") (class "Default")
      (node (ref "CN1") (pin "1") (pinfunction "1_1") (pintype "passive"))
      (node (ref "CN1") (pin "2") (pinfunction "2_2") (pintype "passive"))
      (node (ref "SW1") (pin "3") (pinfunction "NO_3") (pintype "passive"))
    )
    (net (code "112") (name "/NC_Kill_Switch2") (class "Default")
      (node (ref "CN6") (pin "1") (pinfunction "1_1") (pintype "passive"))
      (node (ref "CN6") (pin "2") (pinfunction "2_2") (pintype "passive"))
      (node (ref "SW2") (pin "3") (pinfunction "NO_3") (pintype "passive"))
    )
    (net (code "113") (name "/NO_Kill_Switch1") (class "Default")
      (node (ref "CN1") (pin "3") (pinfunction "3_3") (pintype "passive"))
      (node (ref "CN1") (pin "4") (pinfunction "4_4") (pintype "passive"))
      (node (ref "SW1") (pin "1") (pinfunction "NC_1") (pintype "passive"))
    )
    (net (code "114") (name "/NO_Kill_Switch2") (class "Default")
      (node (ref "CN6") (pin "3") (pinfunction "3_3") (pintype "passive"))
      (node (ref "CN6") (pin "4") (pinfunction "4_4") (pintype "passive"))
      (node (ref "SW2") (pin "1") (pinfunction "NC_1") (pintype "passive"))
    )
    (net (code "115") (name "/S_BAND") (class "Default")
      (node (ref "ANT7") (pin "1") (pinfunction "1_1") (pintype "passive"))
      (node (ref "ANT8") (pin "1") (pinfunction "1_1") (pintype "passive"))
    )
    (net (code "116") (name "/UHF1_BAND") (class "Default")
      (node (ref "ANT3") (pin "1") (pinfunction "1_1") (pintype "passive"))
      (node (ref "ANT4") (pin "1") (pinfunction "1_1") (pintype "passive"))
    )
    (net (code "117") (name "/UHF2_BAND") (class "Default")
      (node (ref "ANT5") (pin "1") (pinfunction "1_1") (pintype "passive"))
      (node (ref "ANT6") (pin "1") (pinfunction "1_1") (pintype "passive"))
    )
    (net (code "118") (name "/VHF_BAND") (class "Default")
      (node (ref "ANT1") (pin "1") (pinfunction "1_1") (pintype "passive"))
      (node (ref "ANT2") (pin "1") (pinfunction "1_1") (pintype "passive"))
    )
    (net (code "119") (name "/V_Charging_Batteries") (class "Default")
      (node (ref "CN5") (pin "1") (pinfunction "1_1") (pintype "passive"))
      (node (ref "CN9") (pin "3") (pinfunction "3_3") (pintype "passive"))
      (node (ref "CN9") (pin "4") (pinfunction "4_4") (pintype "passive"))
    )
    (net (code "120") (name "GND") (class "Default")
      (node (ref "CN10") (pin "10") (pintype "passive"))
      (node (ref "CN10") (pin "11") (pintype "passive"))
      (node (ref "CN10") (pin "12") (pintype "passive"))
      (node (ref "CN10") (pin "7") (pintype "passive"))
      (node (ref "CN10") (pin "8") (pintype "passive"))
      (node (ref "CN10") (pin "9") (pintype "passive"))
      (node (ref "CN2") (pin "0") (pinfunction "0_0") (pintype "passive"))
      (node (ref "CN4") (pin "10") (pintype "passive"))
      (node (ref "CN4") (pin "11") (pintype "passive"))
      (node (ref "CN4") (pin "12") (pintype "passive"))
      (node (ref "CN4") (pin "7") (pintype "passive"))
      (node (ref "CN4") (pin "8") (pintype "passive"))
      (node (ref "CN4") (pin "9") (pintype "passive"))
      (node (ref "CN5") (pin "2") (pinfunction "2_2") (pintype "passive"))
      (node (ref "CN8") (pin "0") (pinfunction "0_0") (pintype "passive"))
      (node (ref "CN9") (pin "1") (pinfunction "1_1") (pintype "passive"))
      (node (ref "CN9") (pin "2") (pinfunction "2_2") (pintype "passive"))
    )
    (net (code "121") (name "unconnected-(CN1-Pad0)") (class "Default")
      (node (ref "CN1") (pin "0") (pinfunction "0_0") (pintype "passive"))
    )
    (net (code "122") (name "unconnected-(CN6-Pad0)") (class "Default")
      (node (ref "CN6") (pin "0") (pinfunction "0_0") (pintype "passive"))
    )
    (net (code "123") (name "unconnected-(CN7-Pad0)") (class "Default")
      (node (ref "CN7") (pin "0") (pinfunction "0_0") (pintype "passive"))
    )
    (net (code "124") (name "unconnected-(CN9-Pad0)") (class "Default")
      (node (ref "CN9") (pin "0") (pinfunction "0_0") (pintype "passive"))
    )
  )
)
